# sch_knx-valve-control_v1_1.net
KiCad netlist of a schematic drawn in EasyEDA
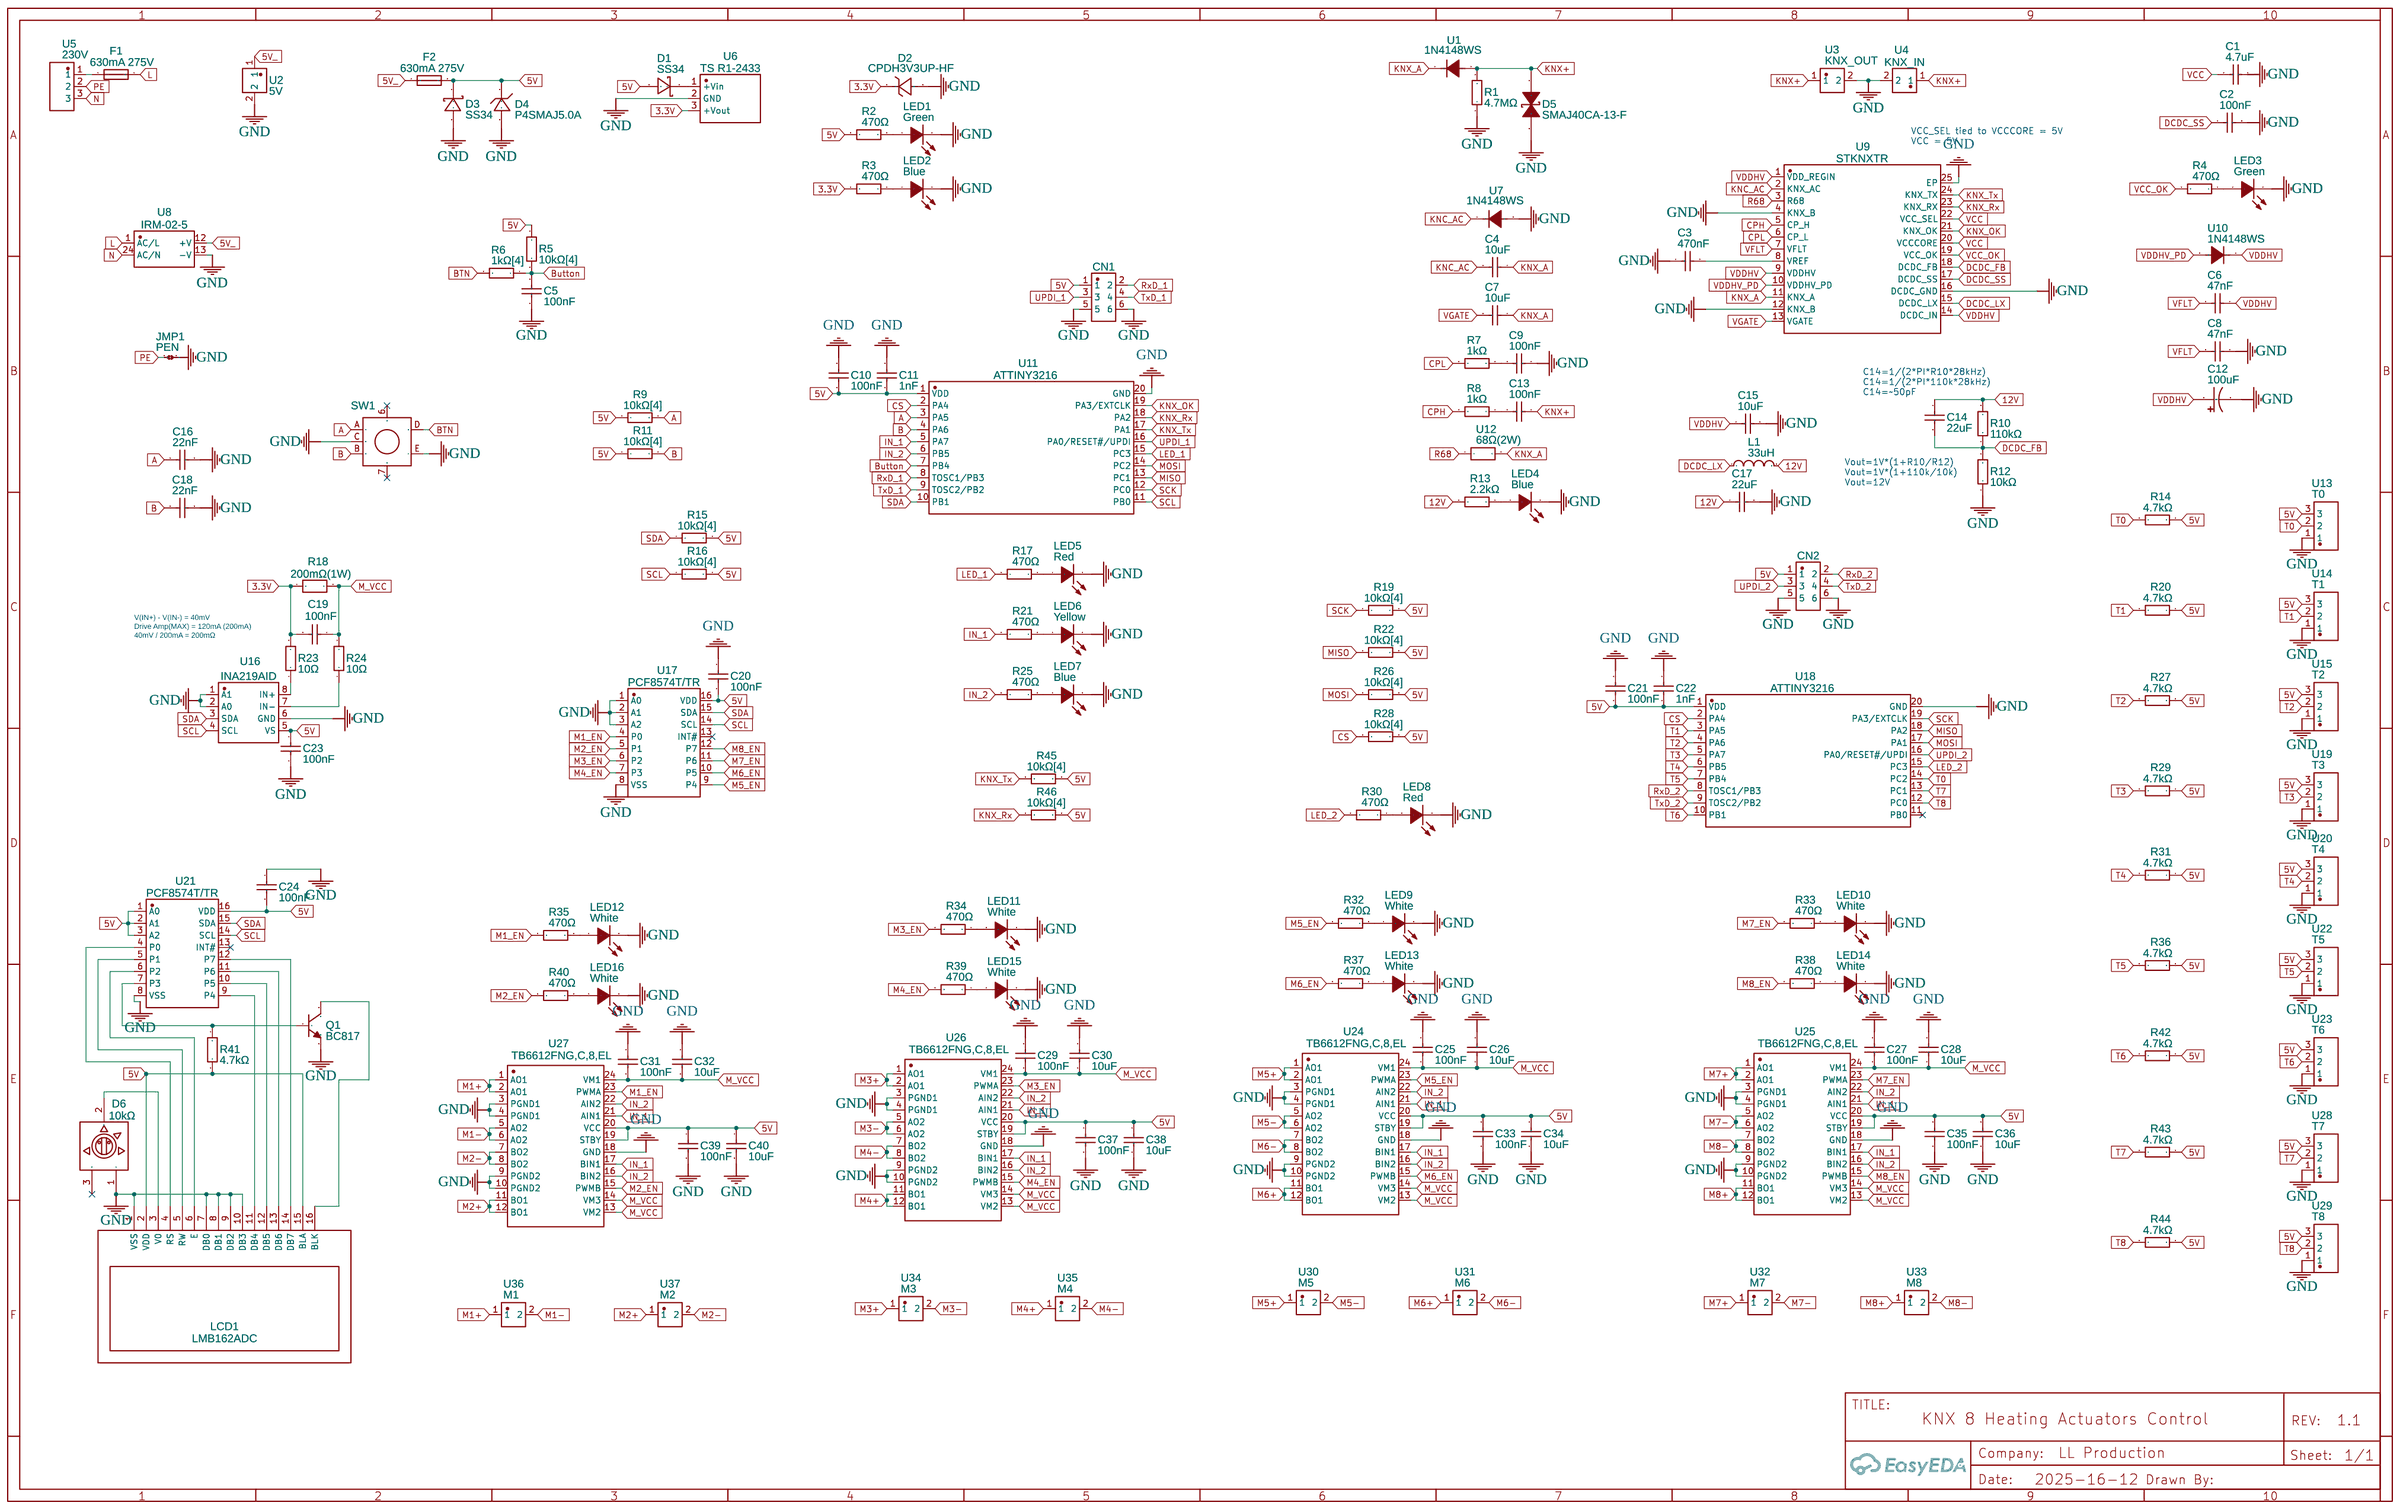
[diagram p0: schematic sheet]

(export (version "E")
  (design (tool "Eeschema 10.0.6"))
  (components
    (comp (ref "C1")
      (value "4.7uF")
      (fields (field (name "Manufacturer Part") "CC0603KRX7R9BB103") (field (name "Manufacturer") "YAGEO"))
      (libsource (lib "") (part "CC0603KRX7R9BB103_3"))
    )
    (comp (ref "C2")
      (value "100nF")
      (fields (field (name "Manufacturer Part") "CC0603KRX7R9BB103") (field (name "Manufacturer") "YAGEO"))
      (libsource (lib "") (part "CC0603KRX7R9BB103"))
    )
    (comp (ref "C3")
      (value "470nF")
      (fields (field (name "Manufacturer Part") "CC0603KRX7R9BB103") (field (name "Manufacturer") "YAGEO"))
      (libsource (lib "") (part "CC0603KRX7R9BB103"))
    )
    (comp (ref "C4")
      (value "10uF")
      (fields (field (name "Manufacturer Part") "CC0603KRX7R9BB103") (field (name "Manufacturer") "YAGEO"))
      (libsource (lib "") (part "CC0603KRX7R9BB103_3"))
    )
    (comp (ref "C5")
      (value "100nF")
      (fields (field (name "Manufacturer Part") "CC0603KRX7R9BB103") (field (name "Manufacturer") "YAGEO"))
      (libsource (lib "") (part "CC0603KRX7R9BB103_1"))
    )
    (comp (ref "C6")
      (value "47nF")
      (fields (field (name "Manufacturer Part") "CC0603KRX7R9BB103") (field (name "Manufacturer") "YAGEO"))
      (libsource (lib "") (part "CC0603KRX7R9BB103_3"))
    )
    (comp (ref "C7")
      (value "10uF")
      (fields (field (name "Manufacturer Part") "CC0603KRX7R9BB103") (field (name "Manufacturer") "YAGEO"))
      (libsource (lib "") (part "CC0603KRX7R9BB103_3"))
    )
    (comp (ref "C8")
      (value "47nF")
      (fields (field (name "Manufacturer Part") "CC0603KRX7R9BB103") (field (name "Manufacturer") "YAGEO"))
      (libsource (lib "") (part "CC0603KRX7R9BB103_3"))
    )
    (comp (ref "C9")
      (value "100nF")
      (fields (field (name "Manufacturer Part") "CC0603KRX7R9BB103") (field (name "Manufacturer") "YAGEO"))
      (libsource (lib "") (part "CC0603KRX7R9BB103_3"))
    )
    (comp (ref "C10")
      (value "100nF")
      (fields (field (name "Manufacturer Part") "CC0603KRX7R9BB103") (field (name "Manufacturer") "YAGEO"))
      (libsource (lib "") (part "CC0603KRX7R9BB103_2"))
    )
    (comp (ref "C11")
      (value "1nF")
      (fields (field (name "Manufacturer Part") "CC0603KRX7R9BB103") (field (name "Manufacturer") "YAGEO"))
      (libsource (lib "") (part "CC0603KRX7R9BB103_2"))
    )
    (comp (ref "C12")
      (value "100uF")
      (fields (field (name "Manufacturer Part") "VEJ101M1HTR-0810") (field (name "Manufacturer") "Lelon(立隆)"))
      (libsource (lib "") (part "VEJ101M1HTR-0810"))
    )
    (comp (ref "C13")
      (value "100nF")
      (fields (field (name "Manufacturer Part") "CC0603KRX7R9BB103") (field (name "Manufacturer") "YAGEO"))
      (libsource (lib "") (part "CC0603KRX7R9BB103_3"))
    )
    (comp (ref "C14")
      (value "22uF")
      (fields (field (name "Manufacturer Part") "CC0603KRX7R9BB103") (field (name "Manufacturer") "YAGEO"))
      (libsource (lib "") (part "CC0603KRX7R9BB103_1"))
    )
    (comp (ref "C15")
      (value "10uF")
      (fields (field (name "Manufacturer Part") "CC0603KRX7R9BB103") (field (name "Manufacturer") "YAGEO"))
      (libsource (lib "") (part "CC0603KRX7R9BB103"))
    )
    (comp (ref "C16")
      (value "22nF")
      (fields (field (name "Manufacturer Part") "CC0603KRX7R9BB103") (field (name "Manufacturer") "YAGEO"))
      (libsource (lib "") (part "CC0603KRX7R9BB103_3"))
    )
    (comp (ref "C17")
      (value "22uF")
      (fields (field (name "Manufacturer Part") "CC0603KRX7R9BB103") (field (name "Manufacturer") "YAGEO"))
      (libsource (lib "") (part "CC0603KRX7R9BB103"))
    )
    (comp (ref "C18")
      (value "22nF")
      (fields (field (name "Manufacturer Part") "CC0603KRX7R9BB103") (field (name "Manufacturer") "YAGEO"))
      (libsource (lib "") (part "CC0603KRX7R9BB103_3"))
    )
    (comp (ref "C19")
      (value "100nF")
      (fields (field (name "Manufacturer Part") "CC0603KRX7R9BB103") (field (name "Manufacturer") "YAGEO"))
      (libsource (lib "") (part "CC0603KRX7R9BB103_3"))
    )
    (comp (ref "C20")
      (value "100nF")
      (fields (field (name "Manufacturer Part") "CC0603KRX7R9BB103") (field (name "Manufacturer") "YAGEO"))
      (libsource (lib "") (part "CC0603KRX7R9BB103_1"))
    )
    (comp (ref "C21")
      (value "100nF")
      (fields (field (name "Manufacturer Part") "CC0603KRX7R9BB103") (field (name "Manufacturer") "YAGEO"))
      (libsource (lib "") (part "CC0603KRX7R9BB103_2"))
    )
    (comp (ref "C22")
      (value "1nF")
      (fields (field (name "Manufacturer Part") "CC0603KRX7R9BB103") (field (name "Manufacturer") "YAGEO"))
      (libsource (lib "") (part "CC0603KRX7R9BB103_2"))
    )
    (comp (ref "C23")
      (value "100nF")
      (fields (field (name "Manufacturer Part") "CC0603KRX7R9BB103") (field (name "Manufacturer") "YAGEO"))
      (libsource (lib "") (part "CC0603KRX7R9BB103_1"))
    )
    (comp (ref "C24")
      (value "100nF")
      (fields (field (name "Manufacturer Part") "CC0603KRX7R9BB103") (field (name "Manufacturer") "YAGEO"))
      (libsource (lib "") (part "CC0603KRX7R9BB103_1"))
    )
    (comp (ref "C25")
      (value "100nF")
      (fields (field (name "Manufacturer Part") "CC0603KRX7R9BB103") (field (name "Manufacturer") "YAGEO"))
      (libsource (lib "") (part "CC0603KRX7R9BB103_1"))
    )
    (comp (ref "C26")
      (value "10uF")
      (fields (field (name "Manufacturer Part") "CC0603KRX7R9BB103") (field (name "Manufacturer") "YAGEO"))
      (libsource (lib "") (part "CC0603KRX7R9BB103_1"))
    )
    (comp (ref "C27")
      (value "100nF")
      (fields (field (name "Manufacturer Part") "CC0603KRX7R9BB103") (field (name "Manufacturer") "YAGEO"))
      (libsource (lib "") (part "CC0603KRX7R9BB103_1"))
    )
    (comp (ref "C28")
      (value "10uF")
      (fields (field (name "Manufacturer Part") "CC0603KRX7R9BB103") (field (name "Manufacturer") "YAGEO"))
      (libsource (lib "") (part "CC0603KRX7R9BB103_1"))
    )
    (comp (ref "C29")
      (value "100nF")
      (fields (field (name "Manufacturer Part") "CC0603KRX7R9BB103") (field (name "Manufacturer") "YAGEO"))
      (libsource (lib "") (part "CC0603KRX7R9BB103_1"))
    )
    (comp (ref "C30")
      (value "10uF")
      (fields (field (name "Manufacturer Part") "CC0603KRX7R9BB103") (field (name "Manufacturer") "YAGEO"))
      (libsource (lib "") (part "CC0603KRX7R9BB103_1"))
    )
    (comp (ref "C31")
      (value "100nF")
      (fields (field (name "Manufacturer Part") "CC0603KRX7R9BB103") (field (name "Manufacturer") "YAGEO"))
      (libsource (lib "") (part "CC0603KRX7R9BB103_1"))
    )
    (comp (ref "C32")
      (value "10uF")
      (fields (field (name "Manufacturer Part") "CC0603KRX7R9BB103") (field (name "Manufacturer") "YAGEO"))
      (libsource (lib "") (part "CC0603KRX7R9BB103_1"))
    )
    (comp (ref "C33")
      (value "100nF")
      (fields (field (name "Manufacturer Part") "CC0603KRX7R9BB103") (field (name "Manufacturer") "YAGEO"))
      (libsource (lib "") (part "CC0603KRX7R9BB103_1"))
    )
    (comp (ref "C34")
      (value "10uF")
      (fields (field (name "Manufacturer Part") "CC0603KRX7R9BB103") (field (name "Manufacturer") "YAGEO"))
      (libsource (lib "") (part "CC0603KRX7R9BB103_1"))
    )
    (comp (ref "C35")
      (value "100nF")
      (fields (field (name "Manufacturer Part") "CC0603KRX7R9BB103") (field (name "Manufacturer") "YAGEO"))
      (libsource (lib "") (part "CC0603KRX7R9BB103_1"))
    )
    (comp (ref "C36")
      (value "10uF")
      (fields (field (name "Manufacturer Part") "CC0603KRX7R9BB103") (field (name "Manufacturer") "YAGEO"))
      (libsource (lib "") (part "CC0603KRX7R9BB103_1"))
    )
    (comp (ref "C37")
      (value "100nF")
      (fields (field (name "Manufacturer Part") "CC0603KRX7R9BB103") (field (name "Manufacturer") "YAGEO"))
      (libsource (lib "") (part "CC0603KRX7R9BB103_1"))
    )
    (comp (ref "C38")
      (value "10uF")
      (fields (field (name "Manufacturer Part") "CC0603KRX7R9BB103") (field (name "Manufacturer") "YAGEO"))
      (libsource (lib "") (part "CC0603KRX7R9BB103_1"))
    )
    (comp (ref "C39")
      (value "100nF")
      (fields (field (name "Manufacturer Part") "CC0603KRX7R9BB103") (field (name "Manufacturer") "YAGEO"))
      (libsource (lib "") (part "CC0603KRX7R9BB103_1"))
    )
    (comp (ref "C40")
      (value "10uF")
      (fields (field (name "Manufacturer Part") "CC0603KRX7R9BB103") (field (name "Manufacturer") "YAGEO"))
      (libsource (lib "") (part "CC0603KRX7R9BB103_1"))
    )
    (comp (ref "CN1")
      (value "321006SG0ABK00A01")
      (fields (field (name "Manufacturer") "JILN(锦凌)"))
      (libsource (lib "") (part "321006SG0ABK00A01"))
    )
    (comp (ref "CN2")
      (value "321006SG0ABK00A01")
      (fields (field (name "Manufacturer") "JILN(锦凌)"))
      (libsource (lib "") (part "321006SG0ABK00A01"))
    )
    (comp (ref "D1")
      (value "SS34")
      (fields (field (name "Manufacturer") "MDD"))
      (libsource (lib "") (part "SS34_C8678_1"))
    )
    (comp (ref "D2")
      (value "CPDH3V3UP-HF")
      (fields (field (name "Manufacturer Part") "SOD-523"))
      (libsource (lib "") (part "SOD-523"))
    )
    (comp (ref "D3")
      (value "SS34")
      (fields (field (name "Manufacturer") "MDD"))
      (libsource (lib "") (part "SS34_C8678"))
    )
    (comp (ref "D4")
      (value "P4SMAJ5.0A")
      (fields
        (field (name "Manufacturer Part") "P4SMAJ12A_R1_00001")
        (field (name "Manufacturer") "PANJIT(强茂)")
      )
      (libsource (lib "") (part "P4SMAJ12A-PEC"))
    )
    (comp (ref "D5")
      (value "SMAJ40CA-13-F")
      (fields (field (name "Manufacturer") "DIODES(美台)"))
      (libsource (lib "") (part "SMAJ40CA-13-F"))
    )
    (comp (ref "D6")
      (value "10kΩ")
      (fields (field (name "Manufacturer Part") "3314G-1-103E") (field (name "Manufacturer") "BOURNS"))
      (libsource (lib "") (part "3314G-1-103E"))
    )
    (comp (ref "F1")
      (value "630mA 275V")
      (fields (field (name "Manufacturer Part") "S1032-F-60.0A") (field (name "Manufacturer") "SART(萨特)"))
      (libsource (lib "") (part "S1032-F-60.0A"))
    )
    (comp (ref "F2")
      (value "630mA 275V")
      (fields (field (name "Manufacturer Part") "S1032-F-60.0A") (field (name "Manufacturer") "SART(萨特)"))
      (libsource (lib "") (part "S1032-F-60.0A"))
    )
    (comp (ref "JMP1") (value "PEN") (libsource (lib "") (part "JMP-2-NO-0603")))
    (comp (ref "L1")
      (value "33uH")
      (fields
        (field (name "Manufacturer Part") "NR5040T330M")
        (field (name "Manufacturer") "TAIYO YUDEN(太诱)")
      )
      (libsource (lib "") (part "NR5040T330M"))
    )
    (comp (ref "LCD1")
      (value "LMB162ADC")
      (fields (field (name "Manufacturer") "TOPWAY"))
      (libsource (lib "") (part "LMB162ADC"))
    )
    (comp (ref "LED1")
      (value "Green")
      (fields (field (name "Manufacturer Part") "SZYY0603R") (field (name "Manufacturer") "yongyu(永裕光电)"))
      (libsource (lib "") (part "SZYY0603R"))
    )
    (comp (ref "LED2")
      (value "Blue")
      (fields (field (name "Manufacturer Part") "SZYY0603R") (field (name "Manufacturer") "yongyu(永裕光电)"))
      (libsource (lib "") (part "SZYY0603R"))
    )
    (comp (ref "LED3")
      (value "Green")
      (fields (field (name "Manufacturer Part") "SZYY0603R") (field (name "Manufacturer") "yongyu(永裕光电)"))
      (libsource (lib "") (part "SZYY0603R"))
    )
    (comp (ref "LED4")
      (value "Blue")
      (fields (field (name "Manufacturer Part") "SZYY0603R") (field (name "Manufacturer") "yongyu(永裕光电)"))
      (libsource (lib "") (part "SZYY0603R"))
    )
    (comp (ref "LED5")
      (value "Red")
      (fields (field (name "Manufacturer Part") "SZYY0603R") (field (name "Manufacturer") "yongyu(永裕光电)"))
      (libsource (lib "") (part "SZYY0603R"))
    )
    (comp (ref "LED6")
      (value "Yellow")
      (fields (field (name "Manufacturer Part") "SZYY0603R") (field (name "Manufacturer") "yongyu(永裕光电)"))
      (libsource (lib "") (part "SZYY0603R"))
    )
    (comp (ref "LED7")
      (value "Blue")
      (fields (field (name "Manufacturer Part") "SZYY0603R") (field (name "Manufacturer") "yongyu(永裕光电)"))
      (libsource (lib "") (part "SZYY0603R"))
    )
    (comp (ref "LED8")
      (value "Red")
      (fields (field (name "Manufacturer Part") "SZYY0603R") (field (name "Manufacturer") "yongyu(永裕光电)"))
      (libsource (lib "") (part "SZYY0603R"))
    )
    (comp (ref "LED9")
      (value "White")
      (fields (field (name "Manufacturer Part") "SZYY0603R") (field (name "Manufacturer") "yongyu(永裕光电)"))
      (libsource (lib "") (part "SZYY0603R"))
    )
    (comp (ref "LED10")
      (value "White")
      (fields (field (name "Manufacturer Part") "SZYY0603R") (field (name "Manufacturer") "yongyu(永裕光电)"))
      (libsource (lib "") (part "SZYY0603R"))
    )
    (comp (ref "LED11")
      (value "White")
      (fields (field (name "Manufacturer Part") "SZYY0603R") (field (name "Manufacturer") "yongyu(永裕光电)"))
      (libsource (lib "") (part "SZYY0603R"))
    )
    (comp (ref "LED12")
      (value "White")
      (fields (field (name "Manufacturer Part") "SZYY0603R") (field (name "Manufacturer") "yongyu(永裕光电)"))
      (libsource (lib "") (part "SZYY0603R"))
    )
    (comp (ref "LED13")
      (value "White")
      (fields (field (name "Manufacturer Part") "SZYY0603R") (field (name "Manufacturer") "yongyu(永裕光电)"))
      (libsource (lib "") (part "SZYY0603R"))
    )
    (comp (ref "LED14")
      (value "White")
      (fields (field (name "Manufacturer Part") "SZYY0603R") (field (name "Manufacturer") "yongyu(永裕光电)"))
      (libsource (lib "") (part "SZYY0603R"))
    )
    (comp (ref "LED15")
      (value "White")
      (fields (field (name "Manufacturer Part") "SZYY0603R") (field (name "Manufacturer") "yongyu(永裕光电)"))
      (libsource (lib "") (part "SZYY0603R"))
    )
    (comp (ref "LED16")
      (value "White")
      (fields (field (name "Manufacturer Part") "SZYY0603R") (field (name "Manufacturer") "yongyu(永裕光电)"))
      (libsource (lib "") (part "SZYY0603R"))
    )
    (comp (ref "Q1")
      (value "BC817")
      (fields (field (name "Manufacturer Part") "BC817-40,215") (field (name "Manufacturer") "Nexperia(安世)"))
      (libsource (lib "") (part "BC817-40,215"))
    )
    (comp (ref "R1")
      (value "4.7MΩ")
      (fields (field (name "Manufacturer Part") "CR0603FA1001G") (field (name "Manufacturer") "LIZ(丽智电子)"))
      (libsource (lib "") (part "CR0603FA1001G_C126900_1"))
    )
    (comp (ref "R2")
      (value "470Ω")
      (fields (field (name "Manufacturer Part") "CR0603FA1001G") (field (name "Manufacturer") "LIZ(丽智电子)"))
      (libsource (lib "") (part "CR0603FA1001G_C126900"))
    )
    (comp (ref "R3")
      (value "470Ω")
      (fields (field (name "Manufacturer Part") "CR0603FA1001G") (field (name "Manufacturer") "LIZ(丽智电子)"))
      (libsource (lib "") (part "CR0603FA1001G_C126900"))
    )
    (comp (ref "R4")
      (value "470Ω")
      (fields (field (name "Manufacturer Part") "CR0603FA1001G") (field (name "Manufacturer") "LIZ(丽智电子)"))
      (libsource (lib "") (part "CR0603FA1001G_C126900"))
    )
    (comp (ref "R5")
      (value "10kΩ[4]")
      (fields
        (field (name "Manufacturer Part") "0402WGF1002TCE")
        (field (name "Manufacturer") "UNI-ROYAL(厚声)")
      )
      (libsource (lib "") (part "0402WGF1002TCE_1"))
    )
    (comp (ref "R6")
      (value "1kΩ[4]")
      (fields
        (field (name "Manufacturer Part") "0402WGF1002TCE")
        (field (name "Manufacturer") "UNI-ROYAL(厚声)")
      )
      (libsource (lib "") (part "0402WGF1002TCE_2"))
    )
    (comp (ref "R7")
      (value "1kΩ")
      (fields (field (name "Manufacturer Part") "CR0603FA1001G") (field (name "Manufacturer") "LIZ(丽智电子)"))
      (libsource (lib "") (part "CR0603FA1001G_C126900"))
    )
    (comp (ref "R8")
      (value "1kΩ")
      (fields (field (name "Manufacturer Part") "CR0603FA1001G") (field (name "Manufacturer") "LIZ(丽智电子)"))
      (libsource (lib "") (part "CR0603FA1001G_C126900"))
    )
    (comp (ref "R9")
      (value "10kΩ[4]")
      (fields
        (field (name "Manufacturer Part") "0402WGF1002TCE")
        (field (name "Manufacturer") "UNI-ROYAL(厚声)")
      )
      (libsource (lib "") (part "0402WGF1002TCE"))
    )
    (comp (ref "R10")
      (value "110kΩ")
      (fields (field (name "Manufacturer Part") "CR0603FA1001G") (field (name "Manufacturer") "LIZ(丽智电子)"))
      (libsource (lib "") (part "CR0603FA1001G_C126900_1"))
    )
    (comp (ref "R11")
      (value "10kΩ[4]")
      (fields
        (field (name "Manufacturer Part") "0402WGF1002TCE")
        (field (name "Manufacturer") "UNI-ROYAL(厚声)")
      )
      (libsource (lib "") (part "0402WGF1002TCE"))
    )
    (comp (ref "R12")
      (value "10kΩ")
      (fields (field (name "Manufacturer Part") "CR0603FA1001G") (field (name "Manufacturer") "LIZ(丽智电子)"))
      (libsource (lib "") (part "CR0603FA1001G_C126900_1"))
    )
    (comp (ref "R13")
      (value "2.2kΩ")
      (fields (field (name "Manufacturer Part") "CR0603FA1001G") (field (name "Manufacturer") "LIZ(丽智电子)"))
      (libsource (lib "") (part "CR0603FA1001G_C126900"))
    )
    (comp (ref "R14")
      (value "4.7kΩ")
      (fields (field (name "Manufacturer Part") "CR0603FA1001G") (field (name "Manufacturer") "LIZ(丽智电子)"))
      (libsource (lib "") (part "CR0603FA1001G_C126900"))
    )
    (comp (ref "R15")
      (value "10kΩ[4]")
      (fields
        (field (name "Manufacturer Part") "0402WGF1002TCE")
        (field (name "Manufacturer") "UNI-ROYAL(厚声)")
      )
      (libsource (lib "") (part "0402WGF1002TCE"))
    )
    (comp (ref "R16")
      (value "10kΩ[4]")
      (fields
        (field (name "Manufacturer Part") "0402WGF1002TCE")
        (field (name "Manufacturer") "UNI-ROYAL(厚声)")
      )
      (libsource (lib "") (part "0402WGF1002TCE"))
    )
    (comp (ref "R17")
      (value "470Ω")
      (fields (field (name "Manufacturer Part") "CR0603FA1001G") (field (name "Manufacturer") "LIZ(丽智电子)"))
      (libsource (lib "") (part "CR0603FA1001G_C126900"))
    )
    (comp (ref "R18")
      (value "200mΩ(1W)")
      (fields (field (name "Manufacturer Part") "SCR1206F1M1") (field (name "Manufacturer") "VO(翔胜)"))
      (libsource (lib "") (part "SCR1206F1M1"))
    )
    (comp (ref "R19")
      (value "10kΩ[4]")
      (fields
        (field (name "Manufacturer Part") "0402WGF1002TCE")
        (field (name "Manufacturer") "UNI-ROYAL(厚声)")
      )
      (libsource (lib "") (part "0402WGF1002TCE"))
    )
    (comp (ref "R20")
      (value "4.7kΩ")
      (fields (field (name "Manufacturer Part") "CR0603FA1001G") (field (name "Manufacturer") "LIZ(丽智电子)"))
      (libsource (lib "") (part "CR0603FA1001G_C126900"))
    )
    (comp (ref "R21")
      (value "470Ω")
      (fields (field (name "Manufacturer Part") "CR0603FA1001G") (field (name "Manufacturer") "LIZ(丽智电子)"))
      (libsource (lib "") (part "CR0603FA1001G_C126900"))
    )
    (comp (ref "R22")
      (value "10kΩ[4]")
      (fields
        (field (name "Manufacturer Part") "0402WGF1002TCE")
        (field (name "Manufacturer") "UNI-ROYAL(厚声)")
      )
      (libsource (lib "") (part "0402WGF1002TCE"))
    )
    (comp (ref "R23")
      (value "10Ω")
      (fields (field (name "Manufacturer Part") "CR0603FA1001G") (field (name "Manufacturer") "LIZ(丽智电子)"))
      (libsource (lib "") (part "CR0603FA1001G_C126900_1"))
    )
    (comp (ref "R24")
      (value "10Ω")
      (fields (field (name "Manufacturer Part") "CR0603FA1001G") (field (name "Manufacturer") "LIZ(丽智电子)"))
      (libsource (lib "") (part "CR0603FA1001G_C126900_1"))
    )
    (comp (ref "R25")
      (value "470Ω")
      (fields (field (name "Manufacturer Part") "CR0603FA1001G") (field (name "Manufacturer") "LIZ(丽智电子)"))
      (libsource (lib "") (part "CR0603FA1001G_C126900"))
    )
    (comp (ref "R26")
      (value "10kΩ[4]")
      (fields
        (field (name "Manufacturer Part") "0402WGF1002TCE")
        (field (name "Manufacturer") "UNI-ROYAL(厚声)")
      )
      (libsource (lib "") (part "0402WGF1002TCE"))
    )
    (comp (ref "R27")
      (value "4.7kΩ")
      (fields (field (name "Manufacturer Part") "CR0603FA1001G") (field (name "Manufacturer") "LIZ(丽智电子)"))
      (libsource (lib "") (part "CR0603FA1001G_C126900"))
    )
    (comp (ref "R28")
      (value "10kΩ[4]")
      (fields
        (field (name "Manufacturer Part") "0402WGF1002TCE")
        (field (name "Manufacturer") "UNI-ROYAL(厚声)")
      )
      (libsource (lib "") (part "0402WGF1002TCE"))
    )
    (comp (ref "R29")
      (value "4.7kΩ")
      (fields (field (name "Manufacturer Part") "CR0603FA1001G") (field (name "Manufacturer") "LIZ(丽智电子)"))
      (libsource (lib "") (part "CR0603FA1001G_C126900"))
    )
    (comp (ref "R30")
      (value "470Ω")
      (fields (field (name "Manufacturer Part") "CR0603FA1001G") (field (name "Manufacturer") "LIZ(丽智电子)"))
      (libsource (lib "") (part "CR0603FA1001G_C126900"))
    )
    (comp (ref "R31")
      (value "4.7kΩ")
      (fields (field (name "Manufacturer Part") "CR0603FA1001G") (field (name "Manufacturer") "LIZ(丽智电子)"))
      (libsource (lib "") (part "CR0603FA1001G_C126900"))
    )
    (comp (ref "R32")
      (value "470Ω")
      (fields (field (name "Manufacturer Part") "CR0603FA1001G") (field (name "Manufacturer") "LIZ(丽智电子)"))
      (libsource (lib "") (part "CR0603FA1001G_C126900"))
    )
    (comp (ref "R33")
      (value "470Ω")
      (fields (field (name "Manufacturer Part") "CR0603FA1001G") (field (name "Manufacturer") "LIZ(丽智电子)"))
      (libsource (lib "") (part "CR0603FA1001G_C126900"))
    )
    (comp (ref "R34")
      (value "470Ω")
      (fields (field (name "Manufacturer Part") "CR0603FA1001G") (field (name "Manufacturer") "LIZ(丽智电子)"))
      (libsource (lib "") (part "CR0603FA1001G_C126900"))
    )
    (comp (ref "R35")
      (value "470Ω")
      (fields (field (name "Manufacturer Part") "CR0603FA1001G") (field (name "Manufacturer") "LIZ(丽智电子)"))
      (libsource (lib "") (part "CR0603FA1001G_C126900"))
    )
    (comp (ref "R36")
      (value "4.7kΩ")
      (fields (field (name "Manufacturer Part") "CR0603FA1001G") (field (name "Manufacturer") "LIZ(丽智电子)"))
      (libsource (lib "") (part "CR0603FA1001G_C126900"))
    )
    (comp (ref "R37")
      (value "470Ω")
      (fields (field (name "Manufacturer Part") "CR0603FA1001G") (field (name "Manufacturer") "LIZ(丽智电子)"))
      (libsource (lib "") (part "CR0603FA1001G_C126900"))
    )
    (comp (ref "R38")
      (value "470Ω")
      (fields (field (name "Manufacturer Part") "CR0603FA1001G") (field (name "Manufacturer") "LIZ(丽智电子)"))
      (libsource (lib "") (part "CR0603FA1001G_C126900"))
    )
    (comp (ref "R39")
      (value "470Ω")
      (fields (field (name "Manufacturer Part") "CR0603FA1001G") (field (name "Manufacturer") "LIZ(丽智电子)"))
      (libsource (lib "") (part "CR0603FA1001G_C126900"))
    )
    (comp (ref "R40")
      (value "470Ω")
      (fields (field (name "Manufacturer Part") "CR0603FA1001G") (field (name "Manufacturer") "LIZ(丽智电子)"))
      (libsource (lib "") (part "CR0603FA1001G_C126900"))
    )
    (comp (ref "R41")
      (value "4.7kΩ")
      (fields (field (name "Manufacturer Part") "CR0603FA1001G") (field (name "Manufacturer") "LIZ(丽智电子)"))
      (libsource (lib "") (part "CR0603FA1001G_C126900_2"))
    )
    (comp (ref "R42")
      (value "4.7kΩ")
      (fields (field (name "Manufacturer Part") "CR0603FA1001G") (field (name "Manufacturer") "LIZ(丽智电子)"))
      (libsource (lib "") (part "CR0603FA1001G_C126900"))
    )
    (comp (ref "R43")
      (value "4.7kΩ")
      (fields (field (name "Manufacturer Part") "CR0603FA1001G") (field (name "Manufacturer") "LIZ(丽智电子)"))
      (libsource (lib "") (part "CR0603FA1001G_C126900"))
    )
    (comp (ref "R44")
      (value "4.7kΩ")
      (fields (field (name "Manufacturer Part") "CR0603FA1001G") (field (name "Manufacturer") "LIZ(丽智电子)"))
      (libsource (lib "") (part "CR0603FA1001G_C126900"))
    )
    (comp (ref "R45")
      (value "10kΩ[4]")
      (fields
        (field (name "Manufacturer Part") "0402WGF1002TCE")
        (field (name "Manufacturer") "UNI-ROYAL(厚声)")
      )
      (libsource (lib "") (part "0402WGF1002TCE"))
    )
    (comp (ref "R46")
      (value "10kΩ[4]")
      (fields
        (field (name "Manufacturer Part") "0402WGF1002TCE")
        (field (name "Manufacturer") "UNI-ROYAL(厚声)")
      )
      (libsource (lib "") (part "0402WGF1002TCE"))
    )
    (comp (ref "SW1")
      (value "EC11L1525G01")
      (fields (field (name "Manufacturer") "ALPSALPINE(阿尔卑斯阿尔派)"))
      (libsource (lib "") (part "EC11L1525G01"))
    )
    (comp (ref "U1")
      (value "1N4148WS")
      (fields (field (name "Manufacturer") "Zhengxin(正芯)"))
      (libsource (lib "") (part "1N4148WS_1"))
    )
    (comp (ref "U2")
      (value "5V")
      (fields (field (name "Manufacturer Part") "2P,间距5.08mm,弹片压线升降式"))
      (libsource (lib "") (part "2P,间距5.08MM,弹片压线升降式_1"))
    )
    (comp (ref "U3")
      (value "KNX_OUT")
      (fields (field (name "Manufacturer Part") "2P,间距5.08mm,弹片压线升降式"))
      (libsource (lib "") (part "2P,间距5.08MM,弹片压线升降式"))
    )
    (comp (ref "U4")
      (value "KNX_IN")
      (fields (field (name "Manufacturer Part") "2P,间距5.08mm,弹片压线升降式"))
      (libsource (lib "") (part "2P,间距5.08MM,弹片压线升降式_2"))
    )
    (comp (ref "U5")
      (value "230V")
      (fields
        (field (name "Manufacturer Part") "DB127V-5.08-3P-GN-S")
        (field (name "Manufacturer") "DIBO(地博电气)")
      )
      (libsource (lib "") (part "DB127V-5.08-3P-GN-S_1"))
    )
    (comp (ref "U6")
      (value "TS R1-2433")
      (fields (field (name "Manufacturer") "TRACO POWER"))
      (libsource (lib "") (part "TS R1-2433"))
    )
    (comp (ref "U7")
      (value "1N4148WS")
      (fields (field (name "Manufacturer") "Zhengxin(正芯)"))
      (libsource (lib "") (part "1N4148WS_1"))
    )
    (comp (ref "U8")
      (value "IRM-02-5")
      (fields (field (name "Manufacturer") "MW(明纬)"))
      (libsource (lib "") (part "IRM-02-5"))
    )
    (comp (ref "U9")
      (value "STKNXTR")
      (fields (field (name "Manufacturer") "ST(意法半导体)"))
      (libsource (lib "") (part "STKNXTR"))
    )
    (comp (ref "U10")
      (value "1N4148WS")
      (fields (field (name "Manufacturer") "Zhengxin(正芯)"))
      (libsource (lib "") (part "1N4148WS"))
    )
    (comp (ref "U11")
      (value "ATTINY3216")
      (fields
        (field (name "Manufacturer Part") "ATTINY1616-SN")
        (field (name "Manufacturer") "MICROCHIP(美国微芯)")
      )
      (libsource (lib "") (part "ATTINY1616-SN_C614136"))
    )
    (comp (ref "U12")
      (value "68Ω(2W)")
      (fields
        (field (name "Manufacturer Part") "HoJLR2512-3W-3.5mR-1%")
        (field (name "Manufacturer") "Milliohm(毫欧)")
      )
      (libsource (lib "") (part "HOJLR2512-3W-3.5MR-1%"))
    )
    (comp (ref "U13")
      (value "T0")
      (fields
        (field (name "Manufacturer Part") "DB127V-5.08-3P-GN-S")
        (field (name "Manufacturer") "DIBO(地博电气)")
      )
      (libsource (lib "") (part "DB127V-5.08-3P-GN-S"))
    )
    (comp (ref "U14")
      (value "T1")
      (fields
        (field (name "Manufacturer Part") "DB127V-5.08-3P-GN-S")
        (field (name "Manufacturer") "DIBO(地博电气)")
      )
      (libsource (lib "") (part "DB127V-5.08-3P-GN-S"))
    )
    (comp (ref "U15")
      (value "T2")
      (fields
        (field (name "Manufacturer Part") "DB127V-5.08-3P-GN-S")
        (field (name "Manufacturer") "DIBO(地博电气)")
      )
      (libsource (lib "") (part "DB127V-5.08-3P-GN-S"))
    )
    (comp (ref "U16")
      (value "INA219AID")
      (fields (field (name "Manufacturer") "TI(德州仪器)"))
      (libsource (lib "") (part "INA219AID"))
    )
    (comp (ref "U17")
      (value "PCF8574T/TR")
      (fields (field (name "Manufacturer") "HGSEMI(华冠)"))
      (libsource (lib "") (part "PCF8574T/TR"))
    )
    (comp (ref "U18")
      (value "ATTINY3216")
      (fields
        (field (name "Manufacturer Part") "ATTINY1616-SN")
        (field (name "Manufacturer") "MICROCHIP(美国微芯)")
      )
      (libsource (lib "") (part "ATTINY1616-SN_C614136"))
    )
    (comp (ref "U19")
      (value "T3")
      (fields
        (field (name "Manufacturer Part") "DB127V-5.08-3P-GN-S")
        (field (name "Manufacturer") "DIBO(地博电气)")
      )
      (libsource (lib "") (part "DB127V-5.08-3P-GN-S"))
    )
    (comp (ref "U20")
      (value "T4")
      (fields
        (field (name "Manufacturer Part") "DB127V-5.08-3P-GN-S")
        (field (name "Manufacturer") "DIBO(地博电气)")
      )
      (libsource (lib "") (part "DB127V-5.08-3P-GN-S"))
    )
    (comp (ref "U21")
      (value "PCF8574T/TR")
      (fields (field (name "Manufacturer") "HGSEMI(华冠)"))
      (libsource (lib "") (part "PCF8574T/TR"))
    )
    (comp (ref "U22")
      (value "T5")
      (fields
        (field (name "Manufacturer Part") "DB127V-5.08-3P-GN-S")
        (field (name "Manufacturer") "DIBO(地博电气)")
      )
      (libsource (lib "") (part "DB127V-5.08-3P-GN-S"))
    )
    (comp (ref "U23")
      (value "T6")
      (fields
        (field (name "Manufacturer Part") "DB127V-5.08-3P-GN-S")
        (field (name "Manufacturer") "DIBO(地博电气)")
      )
      (libsource (lib "") (part "DB127V-5.08-3P-GN-S"))
    )
    (comp (ref "U24")
      (value "TB6612FNG,C,8,EL")
      (fields (field (name "Manufacturer") "TOSHIBA(东芝)"))
      (libsource (lib "") (part "TB6612FNG,C,8,EL"))
    )
    (comp (ref "U25")
      (value "TB6612FNG,C,8,EL")
      (fields (field (name "Manufacturer") "TOSHIBA(东芝)"))
      (libsource (lib "") (part "TB6612FNG,C,8,EL"))
    )
    (comp (ref "U26")
      (value "TB6612FNG,C,8,EL")
      (fields (field (name "Manufacturer") "TOSHIBA(东芝)"))
      (libsource (lib "") (part "TB6612FNG,C,8,EL"))
    )
    (comp (ref "U27")
      (value "TB6612FNG,C,8,EL")
      (fields (field (name "Manufacturer") "TOSHIBA(东芝)"))
      (libsource (lib "") (part "TB6612FNG,C,8,EL"))
    )
    (comp (ref "U28")
      (value "T7")
      (fields
        (field (name "Manufacturer Part") "DB127V-5.08-3P-GN-S")
        (field (name "Manufacturer") "DIBO(地博电气)")
      )
      (libsource (lib "") (part "DB127V-5.08-3P-GN-S"))
    )
    (comp (ref "U29")
      (value "T8")
      (fields
        (field (name "Manufacturer Part") "DB127V-5.08-3P-GN-S")
        (field (name "Manufacturer") "DIBO(地博电气)")
      )
      (libsource (lib "") (part "DB127V-5.08-3P-GN-S"))
    )
    (comp (ref "U30")
      (value "M5")
      (fields (field (name "Manufacturer Part") "2P,间距5.08mm,弹片压线升降式"))
      (libsource (lib "") (part "2P,间距5.08MM,弹片压线升降式"))
    )
    (comp (ref "U31")
      (value "M6")
      (fields (field (name "Manufacturer Part") "2P,间距5.08mm,弹片压线升降式"))
      (libsource (lib "") (part "2P,间距5.08MM,弹片压线升降式"))
    )
    (comp (ref "U32")
      (value "M7")
      (fields (field (name "Manufacturer Part") "2P,间距5.08mm,弹片压线升降式"))
      (libsource (lib "") (part "2P,间距5.08MM,弹片压线升降式"))
    )
    (comp (ref "U33")
      (value "M8")
      (fields (field (name "Manufacturer Part") "2P,间距5.08mm,弹片压线升降式"))
      (libsource (lib "") (part "2P,间距5.08MM,弹片压线升降式"))
    )
    (comp (ref "U34")
      (value "M3")
      (fields (field (name "Manufacturer Part") "2P,间距5.08mm,弹片压线升降式"))
      (libsource (lib "") (part "2P,间距5.08MM,弹片压线升降式"))
    )
    (comp (ref "U35")
      (value "M4")
      (fields (field (name "Manufacturer Part") "2P,间距5.08mm,弹片压线升降式"))
      (libsource (lib "") (part "2P,间距5.08MM,弹片压线升降式"))
    )
    (comp (ref "U36")
      (value "M1")
      (fields (field (name "Manufacturer Part") "2P,间距5.08mm,弹片压线升降式"))
      (libsource (lib "") (part "2P,间距5.08MM,弹片压线升降式"))
    )
    (comp (ref "U37")
      (value "M2")
      (fields (field (name "Manufacturer Part") "2P,间距5.08mm,弹片压线升降式"))
      (libsource (lib "") (part "2P,间距5.08MM,弹片压线升降式"))
    )
  )
  (nets
    (net (code "1") (name "3.3V") (class "Default")
      (node (ref "C19") (pin "2") (pinfunction "2_2") (pintype "input"))
      (node (ref "D2") (pin "1") (pinfunction "K_1") (pintype "unspecified"))
      (node (ref "R18") (pin "1") (pinfunction "1_1") (pintype "unspecified"))
      (node (ref "R23") (pin "2") (pinfunction "2_2") (pintype "input"))
      (node (ref "R3") (pin "2") (pinfunction "2_2") (pintype "input"))
      (node (ref "U6") (pin "3") (pinfunction "+Vout_3") (pintype "unspecified"))
    )
    (net (code "2") (name "5V") (class "Default")
      (node (ref "C10") (pin "1") (pinfunction "1_1") (pintype "input"))
      (node (ref "C11") (pin "1") (pinfunction "1_1") (pintype "input"))
      (node (ref "C20") (pin "2") (pinfunction "2_2") (pintype "input"))
      (node (ref "C21") (pin "1") (pinfunction "1_1") (pintype "input"))
      (node (ref "C22") (pin "1") (pinfunction "1_1") (pintype "input"))
      (node (ref "C23") (pin "1") (pinfunction "1_1") (pintype "input"))
      (node (ref "C24") (pin "2") (pinfunction "2_2") (pintype "input"))
      (node (ref "C33") (pin "1") (pinfunction "1_1") (pintype "input"))
      (node (ref "C34") (pin "1") (pinfunction "1_1") (pintype "input"))
      (node (ref "C35") (pin "1") (pinfunction "1_1") (pintype "input"))
      (node (ref "C36") (pin "1") (pinfunction "1_1") (pintype "input"))
      (node (ref "C37") (pin "1") (pinfunction "1_1") (pintype "input"))
      (node (ref "C38") (pin "1") (pinfunction "1_1") (pintype "input"))
      (node (ref "C39") (pin "1") (pinfunction "1_1") (pintype "input"))
      (node (ref "C40") (pin "1") (pinfunction "1_1") (pintype "input"))
      (node (ref "CN1") (pin "1") (pinfunction "1_1") (pintype "unspecified"))
      (node (ref "CN2") (pin "1") (pinfunction "1_1") (pintype "unspecified"))
      (node (ref "D1") (pin "2") (pinfunction "A_2") (pintype "unspecified"))
      (node (ref "D3") (pin "1") (pinfunction "K_1") (pintype "unspecified"))
      (node (ref "D4") (pin "1") (pinfunction "C_1") (pintype "unspecified"))
      (node (ref "F2") (pin "2") (pinfunction "2_2") (pintype "unspecified"))
      (node (ref "LCD1") (pin "15") (pinfunction "BLA_15") (pintype "unspecified"))
      (node (ref "LCD1") (pin "2") (pinfunction "VDD_2") (pintype "unspecified"))
      (node (ref "R11") (pin "1") (pinfunction "1_1") (pintype "input"))
      (node (ref "R14") (pin "1") (pinfunction "1_1") (pintype "input"))
      (node (ref "R15") (pin "2") (pinfunction "2_2") (pintype "input"))
      (node (ref "R16") (pin "2") (pinfunction "2_2") (pintype "input"))
      (node (ref "R19") (pin "2") (pinfunction "2_2") (pintype "input"))
      (node (ref "R2") (pin "2") (pinfunction "2_2") (pintype "input"))
      (node (ref "R20") (pin "1") (pinfunction "1_1") (pintype "input"))
      (node (ref "R22") (pin "2") (pinfunction "2_2") (pintype "input"))
      (node (ref "R26") (pin "2") (pinfunction "2_2") (pintype "input"))
      (node (ref "R27") (pin "1") (pinfunction "1_1") (pintype "input"))
      (node (ref "R28") (pin "2") (pinfunction "2_2") (pintype "input"))
      (node (ref "R29") (pin "1") (pinfunction "1_1") (pintype "input"))
      (node (ref "R31") (pin "1") (pinfunction "1_1") (pintype "input"))
      (node (ref "R36") (pin "1") (pinfunction "1_1") (pintype "input"))
      (node (ref "R41") (pin "2") (pinfunction "2_2") (pintype "input"))
      (node (ref "R42") (pin "1") (pinfunction "1_1") (pintype "input"))
      (node (ref "R43") (pin "1") (pinfunction "1_1") (pintype "input"))
      (node (ref "R44") (pin "1") (pinfunction "1_1") (pintype "input"))
      (node (ref "R45") (pin "2") (pinfunction "2_2") (pintype "input"))
      (node (ref "R46") (pin "2") (pinfunction "2_2") (pintype "input"))
      (node (ref "R5") (pin "1") (pinfunction "1_1") (pintype "input"))
      (node (ref "R9") (pin "1") (pinfunction "1_1") (pintype "input"))
      (node (ref "U11") (pin "1") (pinfunction "VDD_1") (pintype "unspecified"))
      (node (ref "U13") (pin "3") (pinfunction "3_3") (pintype "unspecified"))
      (node (ref "U14") (pin "3") (pinfunction "3_3") (pintype "unspecified"))
      (node (ref "U15") (pin "3") (pinfunction "3_3") (pintype "unspecified"))
      (node (ref "U16") (pin "5") (pinfunction "VS_5") (pintype "unspecified"))
      (node (ref "U17") (pin "16") (pinfunction "VDD_16") (pintype "unspecified"))
      (node (ref "U18") (pin "1") (pinfunction "VDD_1") (pintype "unspecified"))
      (node (ref "U19") (pin "3") (pinfunction "3_3") (pintype "unspecified"))
      (node (ref "U20") (pin "3") (pinfunction "3_3") (pintype "unspecified"))
      (node (ref "U21") (pin "1") (pinfunction "A0_1") (pintype "unspecified"))
      (node (ref "U21") (pin "16") (pinfunction "VDD_16") (pintype "unspecified"))
      (node (ref "U21") (pin "2") (pinfunction "A1_2") (pintype "unspecified"))
      (node (ref "U21") (pin "3") (pinfunction "A2_3") (pintype "unspecified"))
      (node (ref "U22") (pin "3") (pinfunction "3_3") (pintype "unspecified"))
      (node (ref "U23") (pin "3") (pinfunction "3_3") (pintype "unspecified"))
      (node (ref "U24") (pin "19") (pinfunction "STBY_19") (pintype "unspecified"))
      (node (ref "U24") (pin "20") (pinfunction "VCC_20") (pintype "unspecified"))
      (node (ref "U25") (pin "19") (pinfunction "STBY_19") (pintype "unspecified"))
      (node (ref "U25") (pin "20") (pinfunction "VCC_20") (pintype "unspecified"))
      (node (ref "U26") (pin "19") (pinfunction "STBY_19") (pintype "unspecified"))
      (node (ref "U26") (pin "20") (pinfunction "VCC_20") (pintype "unspecified"))
      (node (ref "U27") (pin "19") (pinfunction "STBY_19") (pintype "unspecified"))
      (node (ref "U27") (pin "20") (pinfunction "VCC_20") (pintype "unspecified"))
      (node (ref "U28") (pin "3") (pinfunction "3_3") (pintype "unspecified"))
      (node (ref "U29") (pin "3") (pinfunction "3_3") (pintype "unspecified"))
    )
    (net (code "3") (name "5V_") (class "Default")
      (node (ref "F2") (pin "1") (pinfunction "1_1") (pintype "unspecified"))
      (node (ref "U2") (pin "1") (pinfunction "1_1") (pintype "unspecified"))
      (node (ref "U8") (pin "12") (pinfunction "+V_12") (pintype "unspecified"))
    )
    (net (code "4") (name "12V") (class "Default")
      (node (ref "C14") (pin "1") (pinfunction "1_1") (pintype "input"))
      (node (ref "C17") (pin "1") (pinfunction "1_1") (pintype "input"))
      (node (ref "L1") (pin "2") (pinfunction "2_2") (pintype "unspecified"))
      (node (ref "R10") (pin "2") (pinfunction "2_2") (pintype "input"))
      (node (ref "R13") (pin "2") (pinfunction "2_2") (pintype "input"))
    )
    (net (code "5") (name "A") (class "Default")
      (node (ref "C16") (pin "2") (pinfunction "2_2") (pintype "input"))
      (node (ref "R9") (pin "2") (pinfunction "2_2") (pintype "input"))
      (node (ref "SW1") (pin "A") (pinfunction "A_A") (pintype "unspecified"))
      (node (ref "U11") (pin "3") (pinfunction "PA5_3") (pintype "unspecified"))
    )
    (net (code "6") (name "B") (class "Default")
      (node (ref "C18") (pin "2") (pinfunction "2_2") (pintype "input"))
      (node (ref "R11") (pin "2") (pinfunction "2_2") (pintype "input"))
      (node (ref "SW1") (pin "B") (pinfunction "B_B") (pintype "unspecified"))
      (node (ref "U11") (pin "4") (pinfunction "PA6_4") (pintype "unspecified"))
    )
    (net (code "7") (name "BTN") (class "Default")
      (node (ref "R6") (pin "2") (pinfunction "2_2") (pintype "input"))
      (node (ref "SW1") (pin "D") (pinfunction "D_D") (pintype "unspecified"))
    )
    (net (code "8") (name "Button") (class "Default")
      (node (ref "C5") (pin "1") (pinfunction "1_1") (pintype "input"))
      (node (ref "R5") (pin "2") (pinfunction "2_2") (pintype "input"))
      (node (ref "R6") (pin "1") (pinfunction "1_1") (pintype "input"))
      (node (ref "U11") (pin "7") (pinfunction "PB4_7") (pintype "unspecified"))
    )
    (net (code "9") (name "CPH") (class "Default")
      (node (ref "R8") (pin "2") (pinfunction "2_2") (pintype "input"))
      (node (ref "U9") (pin "5") (pinfunction "CP_H_5") (pintype "unspecified"))
    )
    (net (code "10") (name "CPL") (class "Default")
      (node (ref "R7") (pin "2") (pinfunction "2_2") (pintype "input"))
      (node (ref "U9") (pin "6") (pinfunction "CP_L_6") (pintype "unspecified"))
    )
    (net (code "11") (name "CS") (class "Default")
      (node (ref "R28") (pin "1") (pinfunction "1_1") (pintype "input"))
      (node (ref "U11") (pin "2") (pinfunction "PA4_2") (pintype "unspecified"))
      (node (ref "U18") (pin "2") (pinfunction "PA4_2") (pintype "unspecified"))
    )
    (net (code "12") (name "DCDC_FB") (class "Default")
      (node (ref "C14") (pin "2") (pinfunction "2_2") (pintype "input"))
      (node (ref "R10") (pin "1") (pinfunction "1_1") (pintype "input"))
      (node (ref "R12") (pin "2") (pinfunction "2_2") (pintype "input"))
      (node (ref "U9") (pin "18") (pinfunction "DCDC_FB_18") (pintype "unspecified"))
    )
    (net (code "13") (name "DCDC_LX") (class "Default")
      (node (ref "L1") (pin "1") (pinfunction "1_1") (pintype "unspecified"))
      (node (ref "U9") (pin "15") (pinfunction "DCDC_LX_15") (pintype "unspecified"))
    )
    (net (code "14") (name "DCDC_SS") (class "Default")
      (node (ref "C2") (pin "1") (pinfunction "1_1") (pintype "input"))
      (node (ref "U9") (pin "17") (pinfunction "DCDC_SS_17") (pintype "unspecified"))
    )
    (net (code "15") (name "GND") (class "Default")
      (node (ref "C1") (pin "1") (pinfunction "1_1") (pintype "input"))
      (node (ref "C10") (pin "2") (pinfunction "2_2") (pintype "input"))
      (node (ref "C11") (pin "2") (pinfunction "2_2") (pintype "input"))
      (node (ref "C12") (pin "2") (pinfunction "2_2") (pintype "unspecified"))
      (node (ref "C15") (pin "2") (pinfunction "2_2") (pintype "input"))
      (node (ref "C16") (pin "1") (pinfunction "1_1") (pintype "input"))
      (node (ref "C17") (pin "2") (pinfunction "2_2") (pintype "input"))
      (node (ref "C18") (pin "1") (pinfunction "1_1") (pintype "input"))
      (node (ref "C2") (pin "2") (pinfunction "2_2") (pintype "input"))
      (node (ref "C20") (pin "1") (pinfunction "1_1") (pintype "input"))
      (node (ref "C21") (pin "2") (pinfunction "2_2") (pintype "input"))
      (node (ref "C22") (pin "2") (pinfunction "2_2") (pintype "input"))
      (node (ref "C23") (pin "2") (pinfunction "2_2") (pintype "input"))
      (node (ref "C24") (pin "1") (pinfunction "1_1") (pintype "input"))
      (node (ref "C25") (pin "1") (pinfunction "1_1") (pintype "input"))
      (node (ref "C26") (pin "1") (pinfunction "1_1") (pintype "input"))
      (node (ref "C27") (pin "1") (pinfunction "1_1") (pintype "input"))
      (node (ref "C28") (pin "1") (pinfunction "1_1") (pintype "input"))
      (node (ref "C29") (pin "1") (pinfunction "1_1") (pintype "input"))
      (node (ref "C3") (pin "1") (pinfunction "1_1") (pintype "input"))
      (node (ref "C30") (pin "1") (pinfunction "1_1") (pintype "input"))
      (node (ref "C31") (pin "1") (pinfunction "1_1") (pintype "input"))
      (node (ref "C32") (pin "1") (pinfunction "1_1") (pintype "input"))
      (node (ref "C33") (pin "2") (pinfunction "2_2") (pintype "input"))
      (node (ref "C34") (pin "2") (pinfunction "2_2") (pintype "input"))
      (node (ref "C35") (pin "2") (pinfunction "2_2") (pintype "input"))
      (node (ref "C36") (pin "2") (pinfunction "2_2") (pintype "input"))
      (node (ref "C37") (pin "2") (pinfunction "2_2") (pintype "input"))
      (node (ref "C38") (pin "2") (pinfunction "2_2") (pintype "input"))
      (node (ref "C39") (pin "2") (pinfunction "2_2") (pintype "input"))
      (node (ref "C40") (pin "2") (pinfunction "2_2") (pintype "input"))
      (node (ref "C5") (pin "2") (pinfunction "2_2") (pintype "input"))
      (node (ref "C8") (pin "1") (pinfunction "1_1") (pintype "input"))
      (node (ref "C9") (pin "1") (pinfunction "1_1") (pintype "input"))
      (node (ref "CN1") (pin "5") (pinfunction "5_5") (pintype "unspecified"))
      (node (ref "CN1") (pin "6") (pinfunction "6_6") (pintype "unspecified"))
      (node (ref "CN2") (pin "5") (pinfunction "5_5") (pintype "unspecified"))
      (node (ref "CN2") (pin "6") (pinfunction "6_6") (pintype "unspecified"))
      (node (ref "D2") (pin "2") (pinfunction "A_2") (pintype "unspecified"))
      (node (ref "D3") (pin "2") (pinfunction "A_2") (pintype "unspecified"))
      (node (ref "D4") (pin "2") (pinfunction "A_2") (pintype "unspecified"))
      (node (ref "D5") (pin "2") (pinfunction "2_2") (pintype "unspecified"))
      (node (ref "D6") (pin "1") (pinfunction "1_1") (pintype "unspecified"))
      (node (ref "JMP1") (pin "2") (pinfunction "2_2") (pintype "unspecified"))
      (node (ref "LCD1") (pin "1") (pinfunction "VSS_1") (pintype "unspecified"))
      (node (ref "LCD1") (pin "10") (pinfunction "DB3_10") (pintype "unspecified"))
      (node (ref "LCD1") (pin "7") (pinfunction "DB0_7") (pintype "unspecified"))
      (node (ref "LCD1") (pin "8") (pinfunction "DB1_8") (pintype "unspecified"))
      (node (ref "LCD1") (pin "9") (pinfunction "DB2_9") (pintype "unspecified"))
      (node (ref "LED1") (pin "2") (pinfunction "-_2") (pintype "unspecified"))
      (node (ref "LED10") (pin "2") (pinfunction "-_2") (pintype "unspecified"))
      (node (ref "LED11") (pin "2") (pinfunction "-_2") (pintype "unspecified"))
      (node (ref "LED12") (pin "2") (pinfunction "-_2") (pintype "unspecified"))
      (node (ref "LED13") (pin "2") (pinfunction "-_2") (pintype "unspecified"))
      (node (ref "LED14") (pin "2") (pinfunction "-_2") (pintype "unspecified"))
      (node (ref "LED15") (pin "2") (pinfunction "-_2") (pintype "unspecified"))
      (node (ref "LED16") (pin "2") (pinfunction "-_2") (pintype "unspecified"))
      (node (ref "LED2") (pin "2") (pinfunction "-_2") (pintype "unspecified"))
      (node (ref "LED3") (pin "2") (pinfunction "-_2") (pintype "unspecified"))
      (node (ref "LED4") (pin "2") (pinfunction "-_2") (pintype "unspecified"))
      (node (ref "LED5") (pin "2") (pinfunction "-_2") (pintype "unspecified"))
      (node (ref "LED6") (pin "2") (pinfunction "-_2") (pintype "unspecified"))
      (node (ref "LED7") (pin "2") (pinfunction "-_2") (pintype "unspecified"))
      (node (ref "LED8") (pin "2") (pinfunction "-_2") (pintype "unspecified"))
      (node (ref "LED9") (pin "2") (pinfunction "-_2") (pintype "unspecified"))
      (node (ref "Q1") (pin "2") (pinfunction "2_2") (pintype "input"))
      (node (ref "R1") (pin "1") (pinfunction "1_1") (pintype "input"))
      (node (ref "R12") (pin "1") (pinfunction "1_1") (pintype "input"))
      (node (ref "SW1") (pin "C") (pinfunction "C_C") (pintype "unspecified"))
      (node (ref "SW1") (pin "E") (pinfunction "E_E") (pintype "unspecified"))
      (node (ref "U11") (pin "20") (pinfunction "GND_20") (pintype "unspecified"))
      (node (ref "U13") (pin "1") (pinfunction "1_1") (pintype "unspecified"))
      (node (ref "U14") (pin "1") (pinfunction "1_1") (pintype "unspecified"))
      (node (ref "U15") (pin "1") (pinfunction "1_1") (pintype "unspecified"))
      (node (ref "U16") (pin "1") (pinfunction "A1_1") (pintype "unspecified"))
      (node (ref "U16") (pin "2") (pinfunction "A0_2") (pintype "unspecified"))
      (node (ref "U16") (pin "6") (pinfunction "GND_6") (pintype "unspecified"))
      (node (ref "U17") (pin "1") (pinfunction "A0_1") (pintype "unspecified"))
      (node (ref "U17") (pin "2") (pinfunction "A1_2") (pintype "unspecified"))
      (node (ref "U17") (pin "3") (pinfunction "A2_3") (pintype "unspecified"))
      (node (ref "U17") (pin "8") (pinfunction "VSS_8") (pintype "unspecified"))
      (node (ref "U18") (pin "20") (pinfunction "GND_20") (pintype "unspecified"))
      (node (ref "U19") (pin "1") (pinfunction "1_1") (pintype "unspecified"))
      (node (ref "U2") (pin "2") (pinfunction "2_2") (pintype "unspecified"))
      (node (ref "U20") (pin "1") (pinfunction "1_1") (pintype "unspecified"))
      (node (ref "U21") (pin "8") (pinfunction "VSS_8") (pintype "unspecified"))
      (node (ref "U22") (pin "1") (pinfunction "1_1") (pintype "unspecified"))
      (node (ref "U23") (pin "1") (pinfunction "1_1") (pintype "unspecified"))
      (node (ref "U24") (pin "10") (pinfunction "PGND2_10") (pintype "unspecified"))
      (node (ref "U24") (pin "18") (pinfunction "GND_18") (pintype "unspecified"))
      (node (ref "U24") (pin "3") (pinfunction "PGND1_3") (pintype "unspecified"))
      (node (ref "U24") (pin "4") (pinfunction "PGND1_4") (pintype "unspecified"))
      (node (ref "U24") (pin "9") (pinfunction "PGND2_9") (pintype "unspecified"))
      (node (ref "U25") (pin "10") (pinfunction "PGND2_10") (pintype "unspecified"))
      (node (ref "U25") (pin "18") (pinfunction "GND_18") (pintype "unspecified"))
      (node (ref "U25") (pin "3") (pinfunction "PGND1_3") (pintype "unspecified"))
      (node (ref "U25") (pin "4") (pinfunction "PGND1_4") (pintype "unspecified"))
      (node (ref "U25") (pin "9") (pinfunction "PGND2_9") (pintype "unspecified"))
      (node (ref "U26") (pin "10") (pinfunction "PGND2_10") (pintype "unspecified"))
      (node (ref "U26") (pin "18") (pinfunction "GND_18") (pintype "unspecified"))
      (node (ref "U26") (pin "3") (pinfunction "PGND1_3") (pintype "unspecified"))
      (node (ref "U26") (pin "4") (pinfunction "PGND1_4") (pintype "unspecified"))
      (node (ref "U26") (pin "9") (pinfunction "PGND2_9") (pintype "unspecified"))
      (node (ref "U27") (pin "10") (pinfunction "PGND2_10") (pintype "unspecified"))
      (node (ref "U27") (pin "18") (pinfunction "GND_18") (pintype "unspecified"))
      (node (ref "U27") (pin "3") (pinfunction "PGND1_3") (pintype "unspecified"))
      (node (ref "U27") (pin "4") (pinfunction "PGND1_4") (pintype "unspecified"))
      (node (ref "U27") (pin "9") (pinfunction "PGND2_9") (pintype "unspecified"))
      (node (ref "U28") (pin "1") (pinfunction "1_1") (pintype "unspecified"))
      (node (ref "U29") (pin "1") (pinfunction "1_1") (pintype "unspecified"))
      (node (ref "U3") (pin "2") (pinfunction "2_2") (pintype "unspecified"))
      (node (ref "U4") (pin "2") (pinfunction "2_2") (pintype "unspecified"))
      (node (ref "U6") (pin "2") (pinfunction "GND_2") (pintype "unspecified"))
      (node (ref "U7") (pin "2") (pinfunction "A_2") (pintype "unspecified"))
      (node (ref "U8") (pin "13") (pinfunction "-V_13") (pintype "unspecified"))
      (node (ref "U9") (pin "12") (pinfunction "KNX_B_12") (pintype "unspecified"))
      (node (ref "U9") (pin "16") (pinfunction "DCDC_GND_16") (pintype "unspecified"))
      (node (ref "U9") (pin "25") (pinfunction "EP_25") (pintype "unspecified"))
      (node (ref "U9") (pin "4") (pinfunction "KNX_B_4") (pintype "unspecified"))
    )
    (net (code "16") (name "IN_1") (class "Default")
      (node (ref "R21") (pin "2") (pinfunction "2_2") (pintype "input"))
      (node (ref "U11") (pin "5") (pinfunction "PA7_5") (pintype "unspecified"))
      (node (ref "U24") (pin "17") (pinfunction "BIN1_17") (pintype "unspecified"))
      (node (ref "U24") (pin "21") (pinfunction "AIN1_21") (pintype "unspecified"))
      (node (ref "U25") (pin "17") (pinfunction "BIN1_17") (pintype "unspecified"))
      (node (ref "U25") (pin "21") (pinfunction "AIN1_21") (pintype "unspecified"))
      (node (ref "U26") (pin "17") (pinfunction "BIN1_17") (pintype "unspecified"))
      (node (ref "U26") (pin "21") (pinfunction "AIN1_21") (pintype "unspecified"))
      (node (ref "U27") (pin "17") (pinfunction "BIN1_17") (pintype "unspecified"))
      (node (ref "U27") (pin "21") (pinfunction "AIN1_21") (pintype "unspecified"))
    )
    (net (code "17") (name "IN_2") (class "Default")
      (node (ref "R25") (pin "2") (pinfunction "2_2") (pintype "input"))
      (node (ref "U11") (pin "6") (pinfunction "PB5_6") (pintype "unspecified"))
      (node (ref "U24") (pin "16") (pinfunction "BIN2_16") (pintype "unspecified"))
      (node (ref "U24") (pin "22") (pinfunction "AIN2_22") (pintype "unspecified"))
      (node (ref "U25") (pin "16") (pinfunction "BIN2_16") (pintype "unspecified"))
      (node (ref "U25") (pin "22") (pinfunction "AIN2_22") (pintype "unspecified"))
      (node (ref "U26") (pin "16") (pinfunction "BIN2_16") (pintype "unspecified"))
      (node (ref "U26") (pin "22") (pinfunction "AIN2_22") (pintype "unspecified"))
      (node (ref "U27") (pin "16") (pinfunction "BIN2_16") (pintype "unspecified"))
      (node (ref "U27") (pin "22") (pinfunction "AIN2_22") (pintype "unspecified"))
    )
    (net (code "18") (name "KNC_AC") (class "Default")
      (node (ref "C4") (pin "2") (pinfunction "2_2") (pintype "input"))
      (node (ref "U7") (pin "1") (pinfunction "K_1") (pintype "unspecified"))
      (node (ref "U9") (pin "2") (pinfunction "KNX_AC_2") (pintype "unspecified"))
    )
    (net (code "19") (name "KNX+") (class "Default")
      (node (ref "C13") (pin "1") (pinfunction "1_1") (pintype "input"))
      (node (ref "D5") (pin "1") (pinfunction "1_1") (pintype "unspecified"))
      (node (ref "R1") (pin "2") (pinfunction "2_2") (pintype "input"))
      (node (ref "U1") (pin "2") (pinfunction "A_2") (pintype "unspecified"))
      (node (ref "U3") (pin "1") (pinfunction "1_1") (pintype "unspecified"))
      (node (ref "U4") (pin "1") (pinfunction "1_1") (pintype "unspecified"))
    )
    (net (code "20") (name "KNX_A") (class "Default")
      (node (ref "C4") (pin "1") (pinfunction "1_1") (pintype "input"))
      (node (ref "C7") (pin "1") (pinfunction "1_1") (pintype "input"))
      (node (ref "U1") (pin "1") (pinfunction "K_1") (pintype "unspecified"))
      (node (ref "U12") (pin "2") (pinfunction "2_2") (pintype "unspecified"))
      (node (ref "U9") (pin "11") (pinfunction "KNX_A_11") (pintype "unspecified"))
    )
    (net (code "21") (name "KNX_OK") (class "Default")
      (node (ref "U11") (pin "19") (pinfunction "PA3/EXTCLK_19") (pintype "unspecified"))
      (node (ref "U9") (pin "21") (pinfunction "KNX_OK_21") (pintype "unspecified"))
    )
    (net (code "22") (name "KNX_Rx") (class "Default")
      (node (ref "R46") (pin "1") (pinfunction "1_1") (pintype "input"))
      (node (ref "U11") (pin "18") (pinfunction "PA2_18") (pintype "unspecified"))
      (node (ref "U9") (pin "23") (pinfunction "KNX_RX_23") (pintype "unspecified"))
    )
    (net (code "23") (name "KNX_Tx") (class "Default")
      (node (ref "R45") (pin "1") (pinfunction "1_1") (pintype "input"))
      (node (ref "U11") (pin "17") (pinfunction "PA1_17") (pintype "unspecified"))
      (node (ref "U9") (pin "24") (pinfunction "KNX_TX_24") (pintype "unspecified"))
    )
    (net (code "24") (name "L") (class "Default")
      (node (ref "F1") (pin "2") (pinfunction "2_2") (pintype "unspecified"))
      (node (ref "U8") (pin "1") (pinfunction "AC/L_1") (pintype "unspecified"))
    )
    (net (code "25") (name "LED_1") (class "Default")
      (node (ref "R17") (pin "2") (pinfunction "2_2") (pintype "input"))
      (node (ref "U11") (pin "15") (pinfunction "PC3_15") (pintype "unspecified"))
    )
    (net (code "26") (name "LED_2") (class "Default")
      (node (ref "R30") (pin "2") (pinfunction "2_2") (pintype "input"))
      (node (ref "U18") (pin "15") (pinfunction "PC3_15") (pintype "unspecified"))
    )
    (net (code "27") (name "M1+") (class "Default")
      (node (ref "U27") (pin "1") (pinfunction "AO1_1") (pintype "unspecified"))
      (node (ref "U27") (pin "2") (pinfunction "AO1_2") (pintype "unspecified"))
      (node (ref "U36") (pin "1") (pinfunction "1_1") (pintype "unspecified"))
    )
    (net (code "28") (name "M1-") (class "Default")
      (node (ref "U27") (pin "5") (pinfunction "AO2_5") (pintype "unspecified"))
      (node (ref "U27") (pin "6") (pinfunction "AO2_6") (pintype "unspecified"))
      (node (ref "U36") (pin "2") (pinfunction "2_2") (pintype "unspecified"))
    )
    (net (code "29") (name "M1_EN") (class "Default")
      (node (ref "R35") (pin "2") (pinfunction "2_2") (pintype "input"))
      (node (ref "U17") (pin "4") (pinfunction "P0_4") (pintype "unspecified"))
      (node (ref "U27") (pin "23") (pinfunction "PWMA_23") (pintype "unspecified"))
    )
    (net (code "30") (name "M2+") (class "Default")
      (node (ref "U27") (pin "11") (pinfunction "BO1_11") (pintype "unspecified"))
      (node (ref "U27") (pin "12") (pinfunction "BO1_12") (pintype "unspecified"))
      (node (ref "U37") (pin "1") (pinfunction "1_1") (pintype "unspecified"))
    )
    (net (code "31") (name "M2-") (class "Default")
      (node (ref "U27") (pin "7") (pinfunction "BO2_7") (pintype "unspecified"))
      (node (ref "U27") (pin "8") (pinfunction "BO2_8") (pintype "unspecified"))
      (node (ref "U37") (pin "2") (pinfunction "2_2") (pintype "unspecified"))
    )
    (net (code "32") (name "M2_EN") (class "Default")
      (node (ref "R40") (pin "2") (pinfunction "2_2") (pintype "input"))
      (node (ref "U17") (pin "5") (pinfunction "P1_5") (pintype "unspecified"))
      (node (ref "U27") (pin "15") (pinfunction "PWMB_15") (pintype "unspecified"))
    )
    (net (code "33") (name "M3+") (class "Default")
      (node (ref "U26") (pin "1") (pinfunction "AO1_1") (pintype "unspecified"))
      (node (ref "U26") (pin "2") (pinfunction "AO1_2") (pintype "unspecified"))
      (node (ref "U34") (pin "1") (pinfunction "1_1") (pintype "unspecified"))
    )
    (net (code "34") (name "M3-") (class "Default")
      (node (ref "U26") (pin "5") (pinfunction "AO2_5") (pintype "unspecified"))
      (node (ref "U26") (pin "6") (pinfunction "AO2_6") (pintype "unspecified"))
      (node (ref "U34") (pin "2") (pinfunction "2_2") (pintype "unspecified"))
    )
    (net (code "35") (name "M3_EN") (class "Default")
      (node (ref "R34") (pin "2") (pinfunction "2_2") (pintype "input"))
      (node (ref "U17") (pin "6") (pinfunction "P2_6") (pintype "unspecified"))
      (node (ref "U26") (pin "23") (pinfunction "PWMA_23") (pintype "unspecified"))
    )
    (net (code "36") (name "M4+") (class "Default")
      (node (ref "U26") (pin "11") (pinfunction "BO1_11") (pintype "unspecified"))
      (node (ref "U26") (pin "12") (pinfunction "BO1_12") (pintype "unspecified"))
      (node (ref "U35") (pin "1") (pinfunction "1_1") (pintype "unspecified"))
    )
    (net (code "37") (name "M4-") (class "Default")
      (node (ref "U26") (pin "7") (pinfunction "BO2_7") (pintype "unspecified"))
      (node (ref "U26") (pin "8") (pinfunction "BO2_8") (pintype "unspecified"))
      (node (ref "U35") (pin "2") (pinfunction "2_2") (pintype "unspecified"))
    )
    (net (code "38") (name "M4_EN") (class "Default")
      (node (ref "R39") (pin "2") (pinfunction "2_2") (pintype "input"))
      (node (ref "U17") (pin "7") (pinfunction "P3_7") (pintype "unspecified"))
      (node (ref "U26") (pin "15") (pinfunction "PWMB_15") (pintype "unspecified"))
    )
    (net (code "39") (name "M5+") (class "Default")
      (node (ref "U24") (pin "1") (pinfunction "AO1_1") (pintype "unspecified"))
      (node (ref "U24") (pin "2") (pinfunction "AO1_2") (pintype "unspecified"))
      (node (ref "U30") (pin "1") (pinfunction "1_1") (pintype "unspecified"))
    )
    (net (code "40") (name "M5-") (class "Default")
      (node (ref "U24") (pin "5") (pinfunction "AO2_5") (pintype "unspecified"))
      (node (ref "U24") (pin "6") (pinfunction "AO2_6") (pintype "unspecified"))
      (node (ref "U30") (pin "2") (pinfunction "2_2") (pintype "unspecified"))
    )
    (net (code "41") (name "M5_EN") (class "Default")
      (node (ref "R32") (pin "2") (pinfunction "2_2") (pintype "input"))
      (node (ref "U17") (pin "9") (pinfunction "P4_9") (pintype "unspecified"))
      (node (ref "U24") (pin "23") (pinfunction "PWMA_23") (pintype "unspecified"))
    )
    (net (code "42") (name "M6+") (class "Default")
      (node (ref "U24") (pin "11") (pinfunction "BO1_11") (pintype "unspecified"))
      (node (ref "U24") (pin "12") (pinfunction "BO1_12") (pintype "unspecified"))
      (node (ref "U31") (pin "1") (pinfunction "1_1") (pintype "unspecified"))
    )
    (net (code "43") (name "M6-") (class "Default")
      (node (ref "U24") (pin "7") (pinfunction "BO2_7") (pintype "unspecified"))
      (node (ref "U24") (pin "8") (pinfunction "BO2_8") (pintype "unspecified"))
      (node (ref "U31") (pin "2") (pinfunction "2_2") (pintype "unspecified"))
    )
    (net (code "44") (name "M6_EN") (class "Default")
      (node (ref "R37") (pin "2") (pinfunction "2_2") (pintype "input"))
      (node (ref "U17") (pin "10") (pinfunction "P5_10") (pintype "unspecified"))
      (node (ref "U24") (pin "15") (pinfunction "PWMB_15") (pintype "unspecified"))
    )
    (net (code "45") (name "M7+") (class "Default")
      (node (ref "U25") (pin "1") (pinfunction "AO1_1") (pintype "unspecified"))
      (node (ref "U25") (pin "2") (pinfunction "AO1_2") (pintype "unspecified"))
      (node (ref "U32") (pin "1") (pinfunction "1_1") (pintype "unspecified"))
    )
    (net (code "46") (name "M7-") (class "Default")
      (node (ref "U25") (pin "5") (pinfunction "AO2_5") (pintype "unspecified"))
      (node (ref "U25") (pin "6") (pinfunction "AO2_6") (pintype "unspecified"))
      (node (ref "U32") (pin "2") (pinfunction "2_2") (pintype "unspecified"))
    )
    (net (code "47") (name "M7_EN") (class "Default")
      (node (ref "R33") (pin "2") (pinfunction "2_2") (pintype "input"))
      (node (ref "U17") (pin "11") (pinfunction "P6_11") (pintype "unspecified"))
      (node (ref "U25") (pin "23") (pinfunction "PWMA_23") (pintype "unspecified"))
    )
    (net (code "48") (name "M8+") (class "Default")
      (node (ref "U25") (pin "11") (pinfunction "BO1_11") (pintype "unspecified"))
      (node (ref "U25") (pin "12") (pinfunction "BO1_12") (pintype "unspecified"))
      (node (ref "U33") (pin "1") (pinfunction "1_1") (pintype "unspecified"))
    )
    (net (code "49") (name "M8-") (class "Default")
      (node (ref "U25") (pin "7") (pinfunction "BO2_7") (pintype "unspecified"))
      (node (ref "U25") (pin "8") (pinfunction "BO2_8") (pintype "unspecified"))
      (node (ref "U33") (pin "2") (pinfunction "2_2") (pintype "unspecified"))
    )
    (net (code "50") (name "M8_EN") (class "Default")
      (node (ref "R38") (pin "2") (pinfunction "2_2") (pintype "input"))
      (node (ref "U17") (pin "12") (pinfunction "P7_12") (pintype "unspecified"))
      (node (ref "U25") (pin "15") (pinfunction "PWMB_15") (pintype "unspecified"))
    )
    (net (code "51") (name "MISO") (class "Default")
      (node (ref "R22") (pin "1") (pinfunction "1_1") (pintype "input"))
      (node (ref "U11") (pin "13") (pinfunction "PC1_13") (pintype "unspecified"))
      (node (ref "U18") (pin "18") (pinfunction "PA2_18") (pintype "unspecified"))
    )
    (net (code "52") (name "MOSI") (class "Default")
      (node (ref "R26") (pin "1") (pinfunction "1_1") (pintype "input"))
      (node (ref "U11") (pin "14") (pinfunction "PC2_14") (pintype "unspecified"))
      (node (ref "U18") (pin "17") (pinfunction "PA1_17") (pintype "unspecified"))
    )
    (net (code "53") (name "M_VCC") (class "Default")
      (node (ref "C19") (pin "1") (pinfunction "1_1") (pintype "input"))
      (node (ref "C25") (pin "2") (pinfunction "2_2") (pintype "input"))
      (node (ref "C26") (pin "2") (pinfunction "2_2") (pintype "input"))
      (node (ref "C27") (pin "2") (pinfunction "2_2") (pintype "input"))
      (node (ref "C28") (pin "2") (pinfunction "2_2") (pintype "input"))
      (node (ref "C29") (pin "2") (pinfunction "2_2") (pintype "input"))
      (node (ref "C30") (pin "2") (pinfunction "2_2") (pintype "input"))
      (node (ref "C31") (pin "2") (pinfunction "2_2") (pintype "input"))
      (node (ref "C32") (pin "2") (pinfunction "2_2") (pintype "input"))
      (node (ref "R18") (pin "2") (pinfunction "2_2") (pintype "unspecified"))
      (node (ref "R24") (pin "2") (pinfunction "2_2") (pintype "input"))
      (node (ref "U24") (pin "13") (pinfunction "VM2_13") (pintype "unspecified"))
      (node (ref "U24") (pin "14") (pinfunction "VM3_14") (pintype "unspecified"))
      (node (ref "U24") (pin "24") (pinfunction "VM1_24") (pintype "unspecified"))
      (node (ref "U25") (pin "13") (pinfunction "VM2_13") (pintype "unspecified"))
      (node (ref "U25") (pin "14") (pinfunction "VM3_14") (pintype "unspecified"))
      (node (ref "U25") (pin "24") (pinfunction "VM1_24") (pintype "unspecified"))
      (node (ref "U26") (pin "13") (pinfunction "VM2_13") (pintype "unspecified"))
      (node (ref "U26") (pin "14") (pinfunction "VM3_14") (pintype "unspecified"))
      (node (ref "U26") (pin "24") (pinfunction "VM1_24") (pintype "unspecified"))
      (node (ref "U27") (pin "13") (pinfunction "VM2_13") (pintype "unspecified"))
      (node (ref "U27") (pin "14") (pinfunction "VM3_14") (pintype "unspecified"))
      (node (ref "U27") (pin "24") (pinfunction "VM1_24") (pintype "unspecified"))
    )
    (net (code "54") (name "N") (class "Default")
      (node (ref "U5") (pin "3") (pinfunction "3_3") (pintype "unspecified"))
      (node (ref "U8") (pin "24") (pinfunction "AC/N_24") (pintype "unspecified"))
    )
    (net (code "55") (name "Net-(C9-Pad2)") (class "Default")
      (node (ref "C9") (pin "2") (pinfunction "2_2") (pintype "input"))
      (node (ref "R7") (pin "1") (pinfunction "1_1") (pintype "input"))
    )
    (net (code "56") (name "Net-(C13-Pad2)") (class "Default")
      (node (ref "C13") (pin "2") (pinfunction "2_2") (pintype "input"))
      (node (ref "R8") (pin "1") (pinfunction "1_1") (pintype "input"))
    )
    (net (code "57") (name "Net-(D1-K)") (class "Default")
      (node (ref "D1") (pin "1") (pinfunction "K_1") (pintype "unspecified"))
      (node (ref "U6") (pin "1") (pinfunction "+Vin_1") (pintype "unspecified"))
    )
    (net (code "58") (name "Net-(F1-Pad1)") (class "Default")
      (node (ref "F1") (pin "1") (pinfunction "1_1") (pintype "unspecified"))
      (node (ref "U5") (pin "1") (pinfunction "1_1") (pintype "unspecified"))
    )
    (net (code "59") (name "Net-(LCD1-BLK)") (class "Default")
      (node (ref "LCD1") (pin "16") (pinfunction "BLK_16") (pintype "unspecified"))
      (node (ref "Q1") (pin "3") (pinfunction "3_3") (pintype "input"))
    )
    (net (code "60") (name "Net-(LCD1-DB4)") (class "Default")
      (node (ref "LCD1") (pin "11") (pinfunction "DB4_11") (pintype "unspecified"))
      (node (ref "U21") (pin "9") (pinfunction "P4_9") (pintype "unspecified"))
    )
    (net (code "61") (name "Net-(LCD1-DB5)") (class "Default")
      (node (ref "LCD1") (pin "12") (pinfunction "DB5_12") (pintype "unspecified"))
      (node (ref "U21") (pin "10") (pinfunction "P5_10") (pintype "unspecified"))
    )
    (net (code "62") (name "Net-(LCD1-DB6)") (class "Default")
      (node (ref "LCD1") (pin "13") (pinfunction "DB6_13") (pintype "unspecified"))
      (node (ref "U21") (pin "11") (pinfunction "P6_11") (pintype "unspecified"))
    )
    (net (code "63") (name "Net-(LCD1-DB7)") (class "Default")
      (node (ref "LCD1") (pin "14") (pinfunction "DB7_14") (pintype "unspecified"))
      (node (ref "U21") (pin "12") (pinfunction "P7_12") (pintype "unspecified"))
    )
    (net (code "64") (name "Net-(LCD1-E)") (class "Default")
      (node (ref "LCD1") (pin "6") (pinfunction "E_6") (pintype "unspecified"))
      (node (ref "U21") (pin "6") (pinfunction "P2_6") (pintype "unspecified"))
    )
    (net (code "65") (name "Net-(LCD1-RS)") (class "Default")
      (node (ref "LCD1") (pin "4") (pinfunction "RS_4") (pintype "unspecified"))
      (node (ref "U21") (pin "4") (pinfunction "P0_4") (pintype "unspecified"))
    )
    (net (code "66") (name "Net-(LCD1-RW)") (class "Default")
      (node (ref "LCD1") (pin "5") (pinfunction "RW_5") (pintype "unspecified"))
      (node (ref "U21") (pin "5") (pinfunction "P1_5") (pintype "unspecified"))
    )
    (net (code "67") (name "Net-(LCD1-V0)") (class "Default")
      (node (ref "D6") (pin "2") (pinfunction "2_2") (pintype "unspecified"))
      (node (ref "LCD1") (pin "3") (pinfunction "V0_3") (pintype "unspecified"))
    )
    (net (code "68") (name "Net-(LED1-+)") (class "Default")
      (node (ref "LED1") (pin "1") (pinfunction "+_1") (pintype "unspecified"))
      (node (ref "R2") (pin "1") (pinfunction "1_1") (pintype "input"))
    )
    (net (code "69") (name "Net-(LED2-+)") (class "Default")
      (node (ref "LED2") (pin "1") (pinfunction "+_1") (pintype "unspecified"))
      (node (ref "R3") (pin "1") (pinfunction "1_1") (pintype "input"))
    )
    (net (code "70") (name "Net-(LED3-+)") (class "Default")
      (node (ref "LED3") (pin "1") (pinfunction "+_1") (pintype "unspecified"))
      (node (ref "R4") (pin "1") (pinfunction "1_1") (pintype "input"))
    )
    (net (code "71") (name "Net-(LED4-+)") (class "Default")
      (node (ref "LED4") (pin "1") (pinfunction "+_1") (pintype "unspecified"))
      (node (ref "R13") (pin "1") (pinfunction "1_1") (pintype "input"))
    )
    (net (code "72") (name "Net-(LED5-+)") (class "Default")
      (node (ref "LED5") (pin "1") (pinfunction "+_1") (pintype "unspecified"))
      (node (ref "R17") (pin "1") (pinfunction "1_1") (pintype "input"))
    )
    (net (code "73") (name "Net-(LED6-+)") (class "Default")
      (node (ref "LED6") (pin "1") (pinfunction "+_1") (pintype "unspecified"))
      (node (ref "R21") (pin "1") (pinfunction "1_1") (pintype "input"))
    )
    (net (code "74") (name "Net-(LED7-+)") (class "Default")
      (node (ref "LED7") (pin "1") (pinfunction "+_1") (pintype "unspecified"))
      (node (ref "R25") (pin "1") (pinfunction "1_1") (pintype "input"))
    )
    (net (code "75") (name "Net-(LED8-+)") (class "Default")
      (node (ref "LED8") (pin "1") (pinfunction "+_1") (pintype "unspecified"))
      (node (ref "R30") (pin "1") (pinfunction "1_1") (pintype "input"))
    )
    (net (code "76") (name "Net-(LED9-+)") (class "Default")
      (node (ref "LED9") (pin "1") (pinfunction "+_1") (pintype "unspecified"))
      (node (ref "R32") (pin "1") (pinfunction "1_1") (pintype "input"))
    )
    (net (code "77") (name "Net-(LED10-+)") (class "Default")
      (node (ref "LED10") (pin "1") (pinfunction "+_1") (pintype "unspecified"))
      (node (ref "R33") (pin "1") (pinfunction "1_1") (pintype "input"))
    )
    (net (code "78") (name "Net-(LED11-+)") (class "Default")
      (node (ref "LED11") (pin "1") (pinfunction "+_1") (pintype "unspecified"))
      (node (ref "R34") (pin "1") (pinfunction "1_1") (pintype "input"))
    )
    (net (code "79") (name "Net-(LED12-+)") (class "Default")
      (node (ref "LED12") (pin "1") (pinfunction "+_1") (pintype "unspecified"))
      (node (ref "R35") (pin "1") (pinfunction "1_1") (pintype "input"))
    )
    (net (code "80") (name "Net-(LED13-+)") (class "Default")
      (node (ref "LED13") (pin "1") (pinfunction "+_1") (pintype "unspecified"))
      (node (ref "R37") (pin "1") (pinfunction "1_1") (pintype "input"))
    )
    (net (code "81") (name "Net-(LED14-+)") (class "Default")
      (node (ref "LED14") (pin "1") (pinfunction "+_1") (pintype "unspecified"))
      (node (ref "R38") (pin "1") (pinfunction "1_1") (pintype "input"))
    )
    (net (code "82") (name "Net-(LED15-+)") (class "Default")
      (node (ref "LED15") (pin "1") (pinfunction "+_1") (pintype "unspecified"))
      (node (ref "R39") (pin "1") (pinfunction "1_1") (pintype "input"))
    )
    (net (code "83") (name "Net-(LED16-+)") (class "Default")
      (node (ref "LED16") (pin "1") (pinfunction "+_1") (pintype "unspecified"))
      (node (ref "R40") (pin "1") (pinfunction "1_1") (pintype "input"))
    )
    (net (code "84") (name "Net-(U9-VREF)") (class "Default")
      (node (ref "C3") (pin "2") (pinfunction "2_2") (pintype "input"))
      (node (ref "U9") (pin "8") (pinfunction "VREF_8") (pintype "unspecified"))
    )
    (net (code "85") (name "Net-(U16-IN+)") (class "Default")
      (node (ref "R23") (pin "1") (pinfunction "1_1") (pintype "input"))
      (node (ref "U16") (pin "8") (pinfunction "IN+_8") (pintype "unspecified"))
    )
    (net (code "86") (name "Net-(U16-IN-)") (class "Default")
      (node (ref "R24") (pin "1") (pinfunction "1_1") (pintype "input"))
      (node (ref "U16") (pin "7") (pinfunction "IN-_7") (pintype "unspecified"))
    )
    (net (code "87") (name "Net-(U21-P3)") (class "Default")
      (node (ref "Q1") (pin "1") (pinfunction "1_1") (pintype "input"))
      (node (ref "R41") (pin "1") (pinfunction "1_1") (pintype "input"))
      (node (ref "U21") (pin "7") (pinfunction "P3_7") (pintype "unspecified"))
    )
    (net (code "88") (name "PE") (class "Default")
      (node (ref "JMP1") (pin "1") (pinfunction "1_1") (pintype "unspecified"))
      (node (ref "U5") (pin "2") (pinfunction "2_2") (pintype "unspecified"))
    )
    (net (code "89") (name "R68") (class "Default")
      (node (ref "U12") (pin "1") (pinfunction "1_1") (pintype "unspecified"))
      (node (ref "U9") (pin "3") (pinfunction "R68_3") (pintype "unspecified"))
    )
    (net (code "90") (name "RxD_1") (class "Default")
      (node (ref "CN1") (pin "2") (pinfunction "2_2") (pintype "unspecified"))
      (node (ref "U11") (pin "8") (pinfunction "TOSC1/PB3_8") (pintype "unspecified"))
    )
    (net (code "91") (name "RxD_2") (class "Default")
      (node (ref "CN2") (pin "2") (pinfunction "2_2") (pintype "unspecified"))
      (node (ref "U18") (pin "8") (pinfunction "TOSC1/PB3_8") (pintype "unspecified"))
    )
    (net (code "92") (name "SCK") (class "Default")
      (node (ref "R19") (pin "1") (pinfunction "1_1") (pintype "input"))
      (node (ref "U11") (pin "12") (pinfunction "PC0_12") (pintype "unspecified"))
      (node (ref "U18") (pin "19") (pinfunction "PA3/EXTCLK_19") (pintype "unspecified"))
    )
    (net (code "93") (name "SCL") (class "Default")
      (node (ref "R16") (pin "1") (pinfunction "1_1") (pintype "input"))
      (node (ref "U11") (pin "11") (pinfunction "PB0_11") (pintype "unspecified"))
      (node (ref "U16") (pin "4") (pinfunction "SCL_4") (pintype "unspecified"))
      (node (ref "U17") (pin "14") (pinfunction "SCL_14") (pintype "unspecified"))
      (node (ref "U21") (pin "14") (pinfunction "SCL_14") (pintype "unspecified"))
    )
    (net (code "94") (name "SDA") (class "Default")
      (node (ref "R15") (pin "1") (pinfunction "1_1") (pintype "input"))
      (node (ref "U11") (pin "10") (pinfunction "PB1_10") (pintype "unspecified"))
      (node (ref "U16") (pin "3") (pinfunction "SDA_3") (pintype "unspecified"))
      (node (ref "U17") (pin "15") (pinfunction "SDA_15") (pintype "unspecified"))
      (node (ref "U21") (pin "15") (pinfunction "SDA_15") (pintype "unspecified"))
    )
    (net (code "95") (name "T0") (class "Default")
      (node (ref "R14") (pin "2") (pinfunction "2_2") (pintype "input"))
      (node (ref "U13") (pin "2") (pinfunction "2_2") (pintype "unspecified"))
      (node (ref "U18") (pin "14") (pinfunction "PC2_14") (pintype "unspecified"))
    )
    (net (code "96") (name "T1") (class "Default")
      (node (ref "R20") (pin "2") (pinfunction "2_2") (pintype "input"))
      (node (ref "U14") (pin "2") (pinfunction "2_2") (pintype "unspecified"))
      (node (ref "U18") (pin "3") (pinfunction "PA5_3") (pintype "unspecified"))
    )
    (net (code "97") (name "T2") (class "Default")
      (node (ref "R27") (pin "2") (pinfunction "2_2") (pintype "input"))
      (node (ref "U15") (pin "2") (pinfunction "2_2") (pintype "unspecified"))
      (node (ref "U18") (pin "4") (pinfunction "PA6_4") (pintype "unspecified"))
    )
    (net (code "98") (name "T3") (class "Default")
      (node (ref "R29") (pin "2") (pinfunction "2_2") (pintype "input"))
      (node (ref "U18") (pin "5") (pinfunction "PA7_5") (pintype "unspecified"))
      (node (ref "U19") (pin "2") (pinfunction "2_2") (pintype "unspecified"))
    )
    (net (code "99") (name "T4") (class "Default")
      (node (ref "R31") (pin "2") (pinfunction "2_2") (pintype "input"))
      (node (ref "U18") (pin "6") (pinfunction "PB5_6") (pintype "unspecified"))
      (node (ref "U20") (pin "2") (pinfunction "2_2") (pintype "unspecified"))
    )
    (net (code "100") (name "T5") (class "Default")
      (node (ref "R36") (pin "2") (pinfunction "2_2") (pintype "input"))
      (node (ref "U18") (pin "7") (pinfunction "PB4_7") (pintype "unspecified"))
      (node (ref "U22") (pin "2") (pinfunction "2_2") (pintype "unspecified"))
    )
    (net (code "101") (name "T6") (class "Default")
      (node (ref "R42") (pin "2") (pinfunction "2_2") (pintype "input"))
      (node (ref "U18") (pin "10") (pinfunction "PB1_10") (pintype "unspecified"))
      (node (ref "U23") (pin "2") (pinfunction "2_2") (pintype "unspecified"))
    )
    (net (code "102") (name "T7") (class "Default")
      (node (ref "R43") (pin "2") (pinfunction "2_2") (pintype "input"))
      (node (ref "U18") (pin "13") (pinfunction "PC1_13") (pintype "unspecified"))
      (node (ref "U28") (pin "2") (pinfunction "2_2") (pintype "unspecified"))
    )
    (net (code "103") (name "T8") (class "Default")
      (node (ref "R44") (pin "2") (pinfunction "2_2") (pintype "input"))
      (node (ref "U18") (pin "12") (pinfunction "PC0_12") (pintype "unspecified"))
      (node (ref "U29") (pin "2") (pinfunction "2_2") (pintype "unspecified"))
    )
    (net (code "104") (name "TxD_1") (class "Default")
      (node (ref "CN1") (pin "4") (pinfunction "4_4") (pintype "unspecified"))
      (node (ref "U11") (pin "9") (pinfunction "TOSC2/PB2_9") (pintype "unspecified"))
    )
    (net (code "105") (name "TxD_2") (class "Default")
      (node (ref "CN2") (pin "4") (pinfunction "4_4") (pintype "unspecified"))
      (node (ref "U18") (pin "9") (pinfunction "TOSC2/PB2_9") (pintype "unspecified"))
    )
    (net (code "106") (name "UPDI_1") (class "Default")
      (node (ref "CN1") (pin "3") (pinfunction "3_3") (pintype "unspecified"))
      (node (ref "U11") (pin "16") (pinfunction "PA0/RESET#/UPDI_16") (pintype "unspecified"))
    )
    (net (code "107") (name "UPDI_2") (class "Default")
      (node (ref "CN2") (pin "3") (pinfunction "3_3") (pintype "unspecified"))
      (node (ref "U18") (pin "16") (pinfunction "PA0/RESET#/UPDI_16") (pintype "unspecified"))
    )
    (net (code "108") (name "VCC") (class "Default")
      (node (ref "C1") (pin "2") (pinfunction "2_2") (pintype "input"))
      (node (ref "U9") (pin "20") (pinfunction "VCCCORE_20") (pintype "unspecified"))
      (node (ref "U9") (pin "22") (pinfunction "VCC_SEL_22") (pintype "unspecified"))
    )
    (net (code "109") (name "VCC_OK") (class "Default")
      (node (ref "R4") (pin "2") (pinfunction "2_2") (pintype "input"))
      (node (ref "U9") (pin "19") (pinfunction "VCC_OK_19") (pintype "unspecified"))
    )
    (net (code "110") (name "VDDHV") (class "Default")
      (node (ref "C12") (pin "1") (pinfunction "1_1") (pintype "unspecified"))
      (node (ref "C15") (pin "1") (pinfunction "1_1") (pintype "input"))
      (node (ref "C6") (pin "1") (pinfunction "1_1") (pintype "input"))
      (node (ref "U10") (pin "1") (pinfunction "K_1") (pintype "unspecified"))
      (node (ref "U9") (pin "1") (pinfunction "VDD_REGIN_1") (pintype "unspecified"))
      (node (ref "U9") (pin "14") (pinfunction "DCDC_IN_14") (pintype "unspecified"))
      (node (ref "U9") (pin "9") (pinfunction "VDDHV_9") (pintype "unspecified"))
    )
    (net (code "111") (name "VDDHV_PD") (class "Default")
      (node (ref "U10") (pin "2") (pinfunction "A_2") (pintype "unspecified"))
      (node (ref "U9") (pin "10") (pinfunction "VDDHV_PD_10") (pintype "unspecified"))
    )
    (net (code "112") (name "VFLT") (class "Default")
      (node (ref "C6") (pin "2") (pinfunction "2_2") (pintype "input"))
      (node (ref "C8") (pin "2") (pinfunction "2_2") (pintype "input"))
      (node (ref "U9") (pin "7") (pinfunction "VFLT_7") (pintype "unspecified"))
    )
    (net (code "113") (name "VGATE") (class "Default")
      (node (ref "C7") (pin "2") (pinfunction "2_2") (pintype "input"))
      (node (ref "U9") (pin "13") (pinfunction "VGATE_13") (pintype "unspecified"))
    )
    (net (code "114") (name "unconnected-(D6-Pad3)") (class "Default")
      (node (ref "D6") (pin "3") (pinfunction "3_3") (pintype "unspecified+no_connect"))
    )
    (net (code "115") (name "unconnected-(SW1-EH-Pad6)") (class "Default")
      (node (ref "SW1") (pin "6") (pinfunction "EH_6") (pintype "unspecified+no_connect"))
    )
    (net (code "116") (name "unconnected-(SW1-EH-Pad7)") (class "Default")
      (node (ref "SW1") (pin "7") (pinfunction "EH_7") (pintype "unspecified+no_connect"))
    )
    (net (code "117") (name "unconnected-(U17-INT#-Pad13)") (class "Default")
      (node (ref "U17") (pin "13") (pinfunction "INT#_13") (pintype "unspecified+no_connect"))
    )
    (net (code "118") (name "unconnected-(U18-PB0-Pad11)") (class "Default")
      (node (ref "U18") (pin "11") (pinfunction "PB0_11") (pintype "unspecified+no_connect"))
    )
    (net (code "119") (name "unconnected-(U21-INT#-Pad13)") (class "Default")
      (node (ref "U21") (pin "13") (pinfunction "INT#_13") (pintype "unspecified+no_connect"))
    )
  )
)
